# Simple_Motherboard.net
KiCad netlist of a schematic drawn in EAGLE
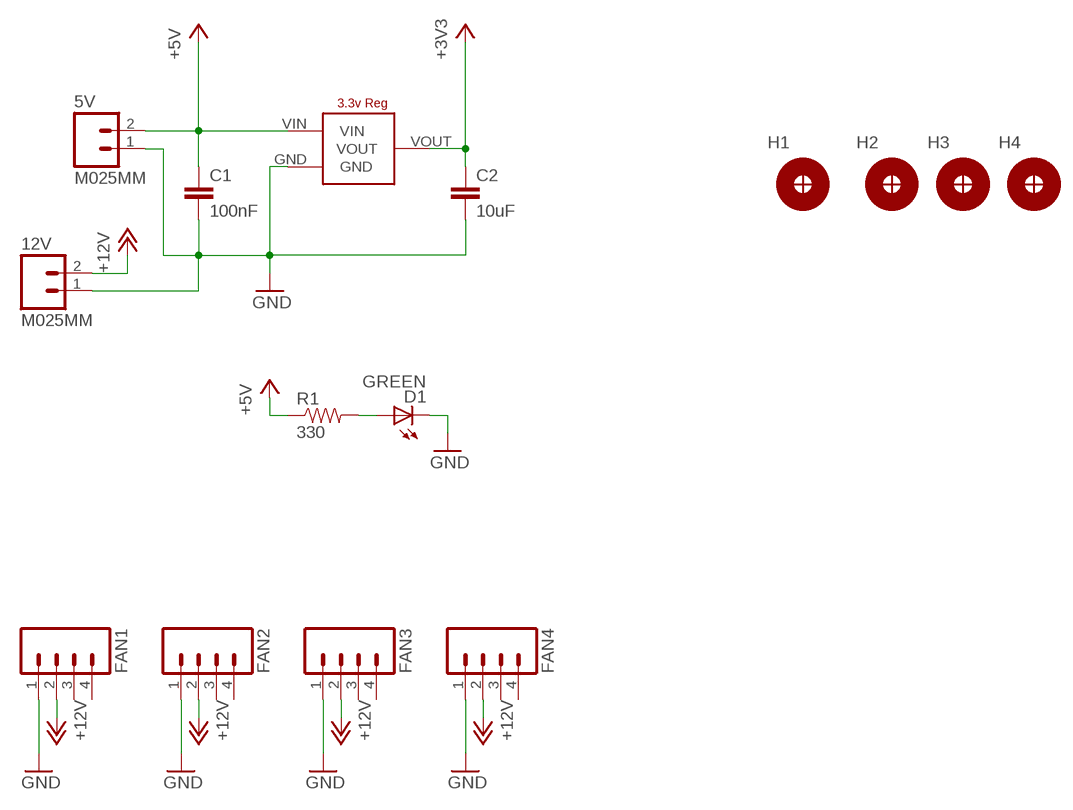
[diagram p0: schematic, sheet 1]
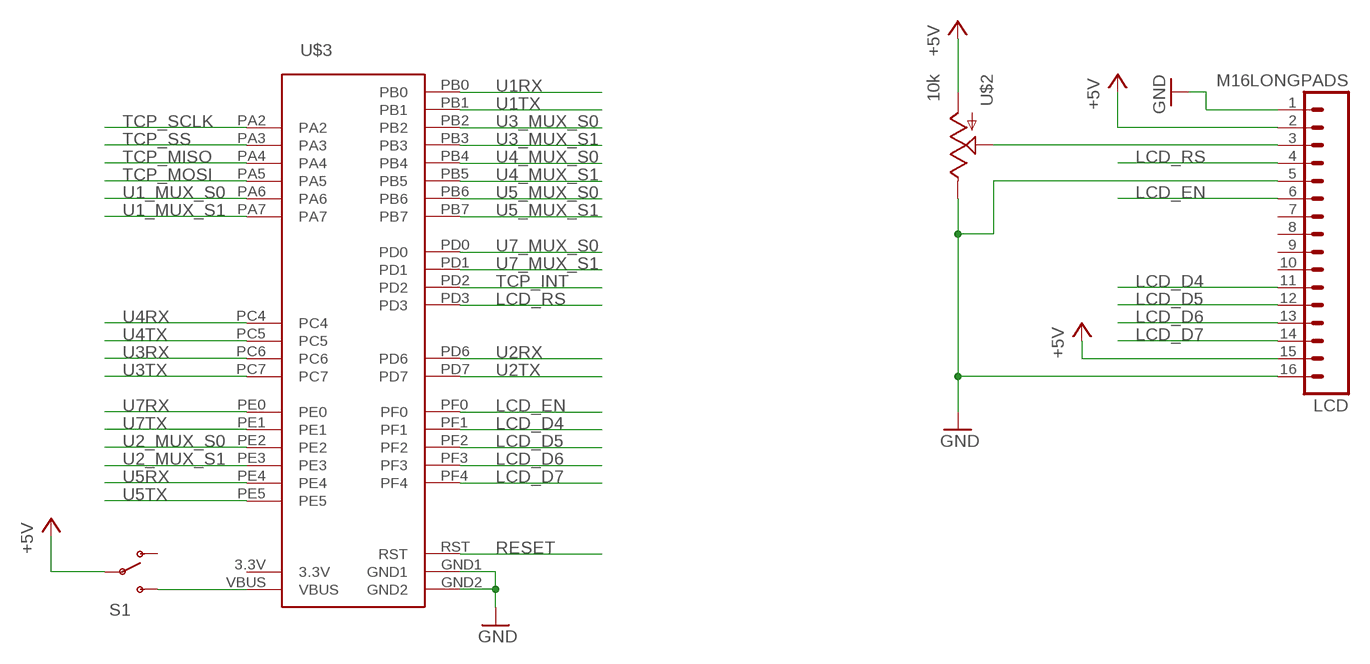
[diagram p1: schematic, sheet 2]
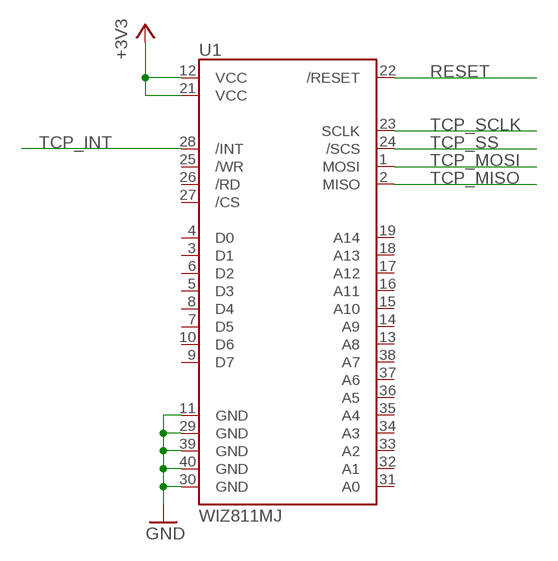
[diagram p2: schematic, sheet 3]
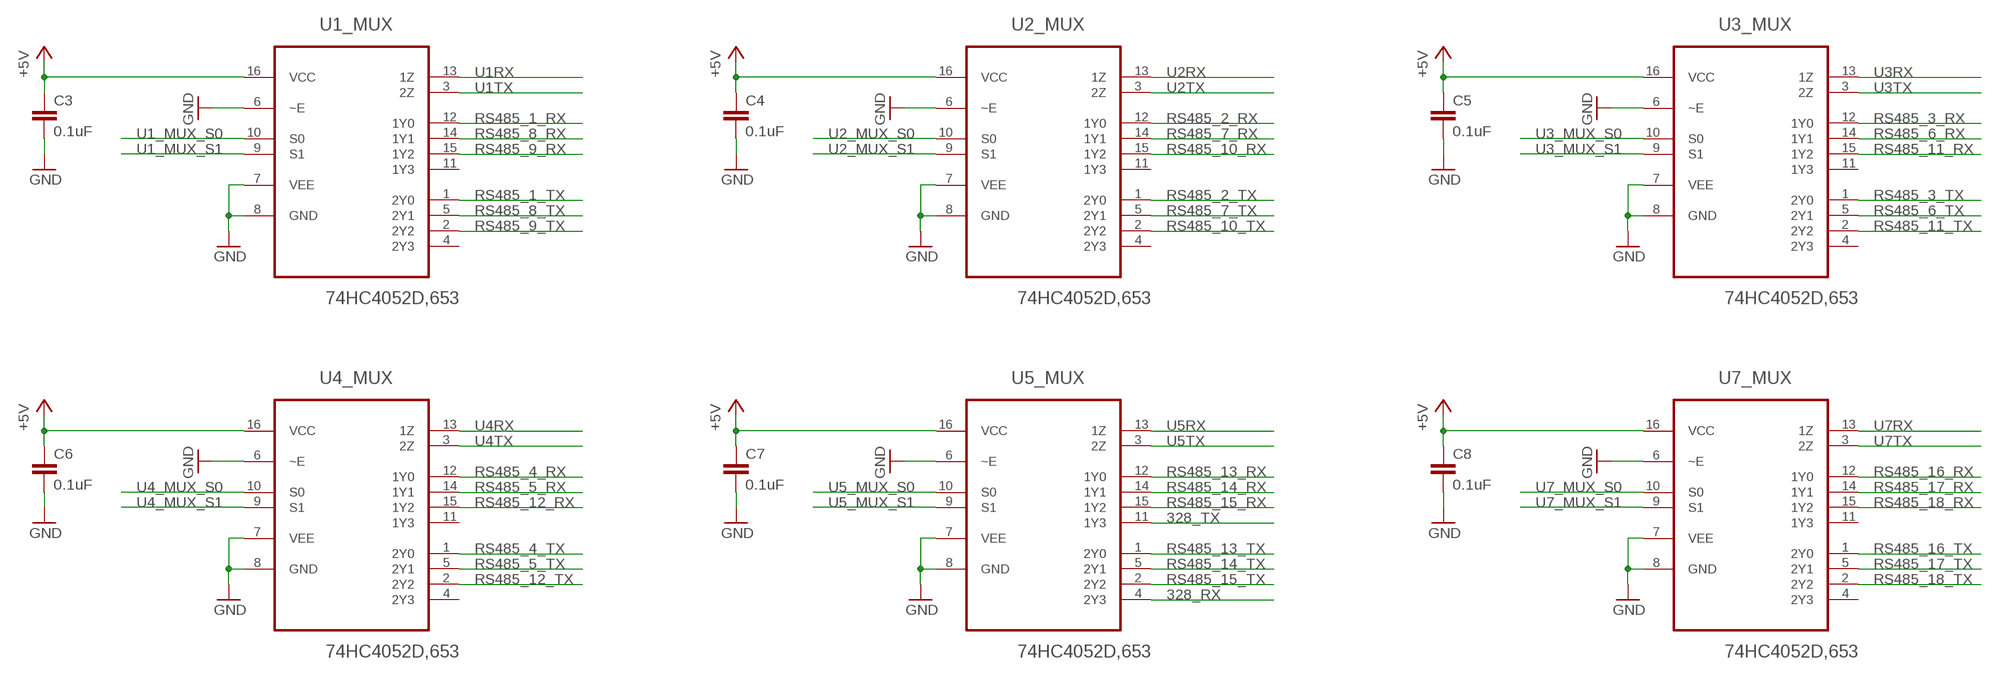
[diagram p3: schematic, sheet 4]
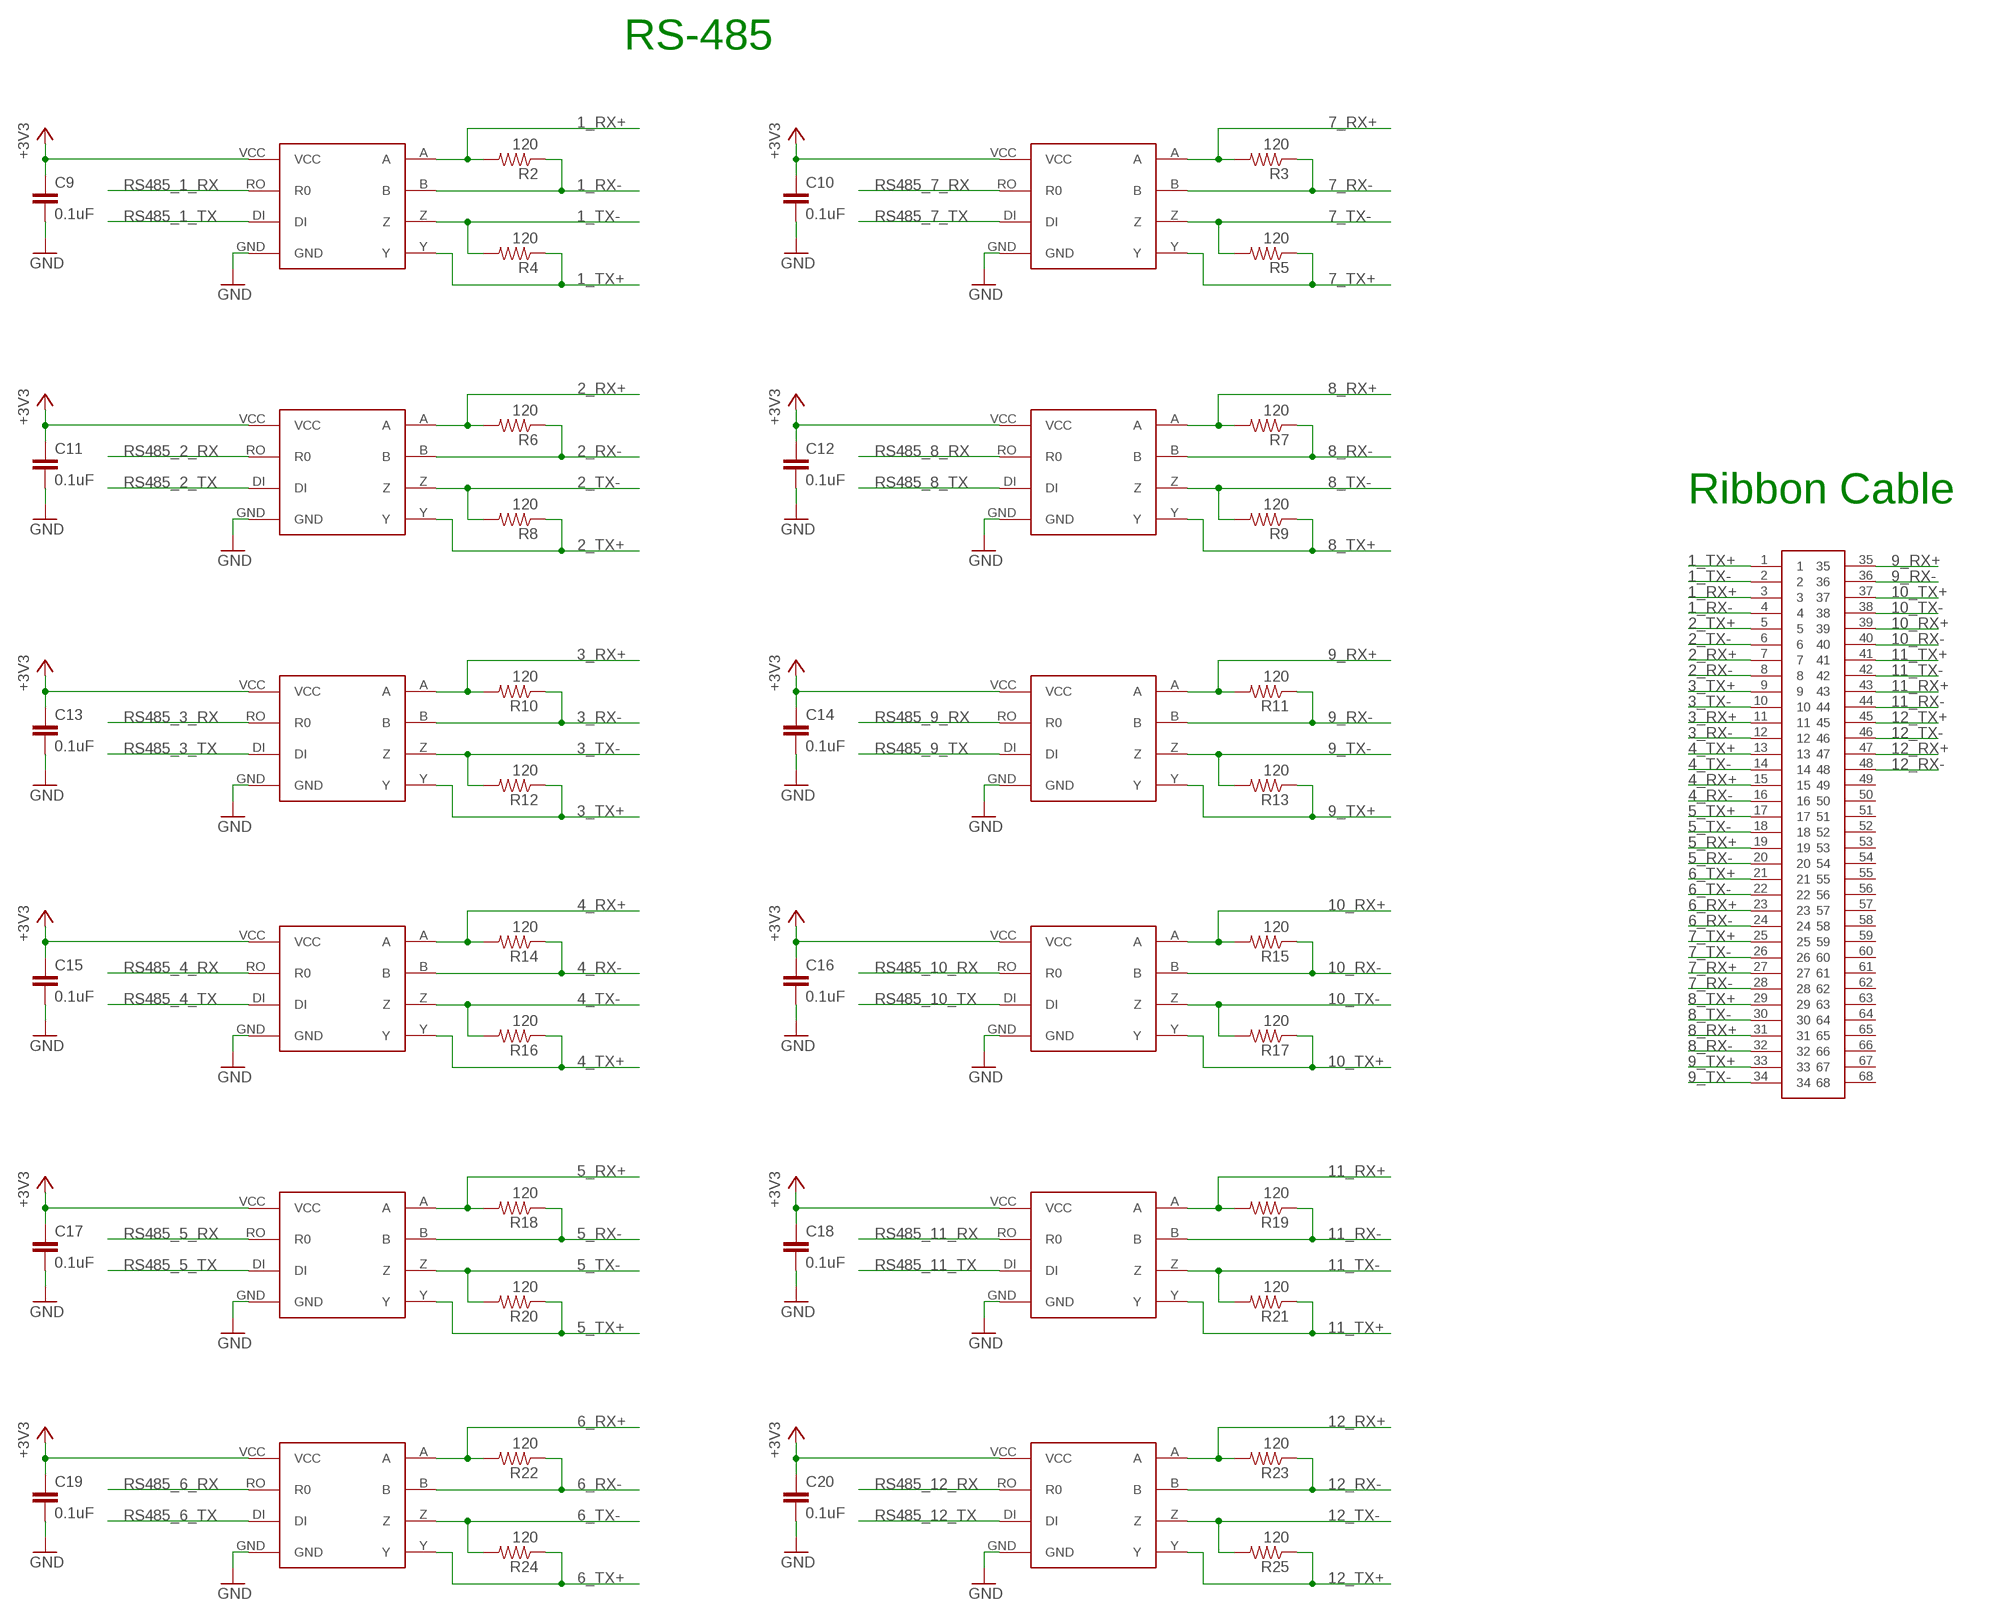
[diagram p4: schematic, sheet 5]
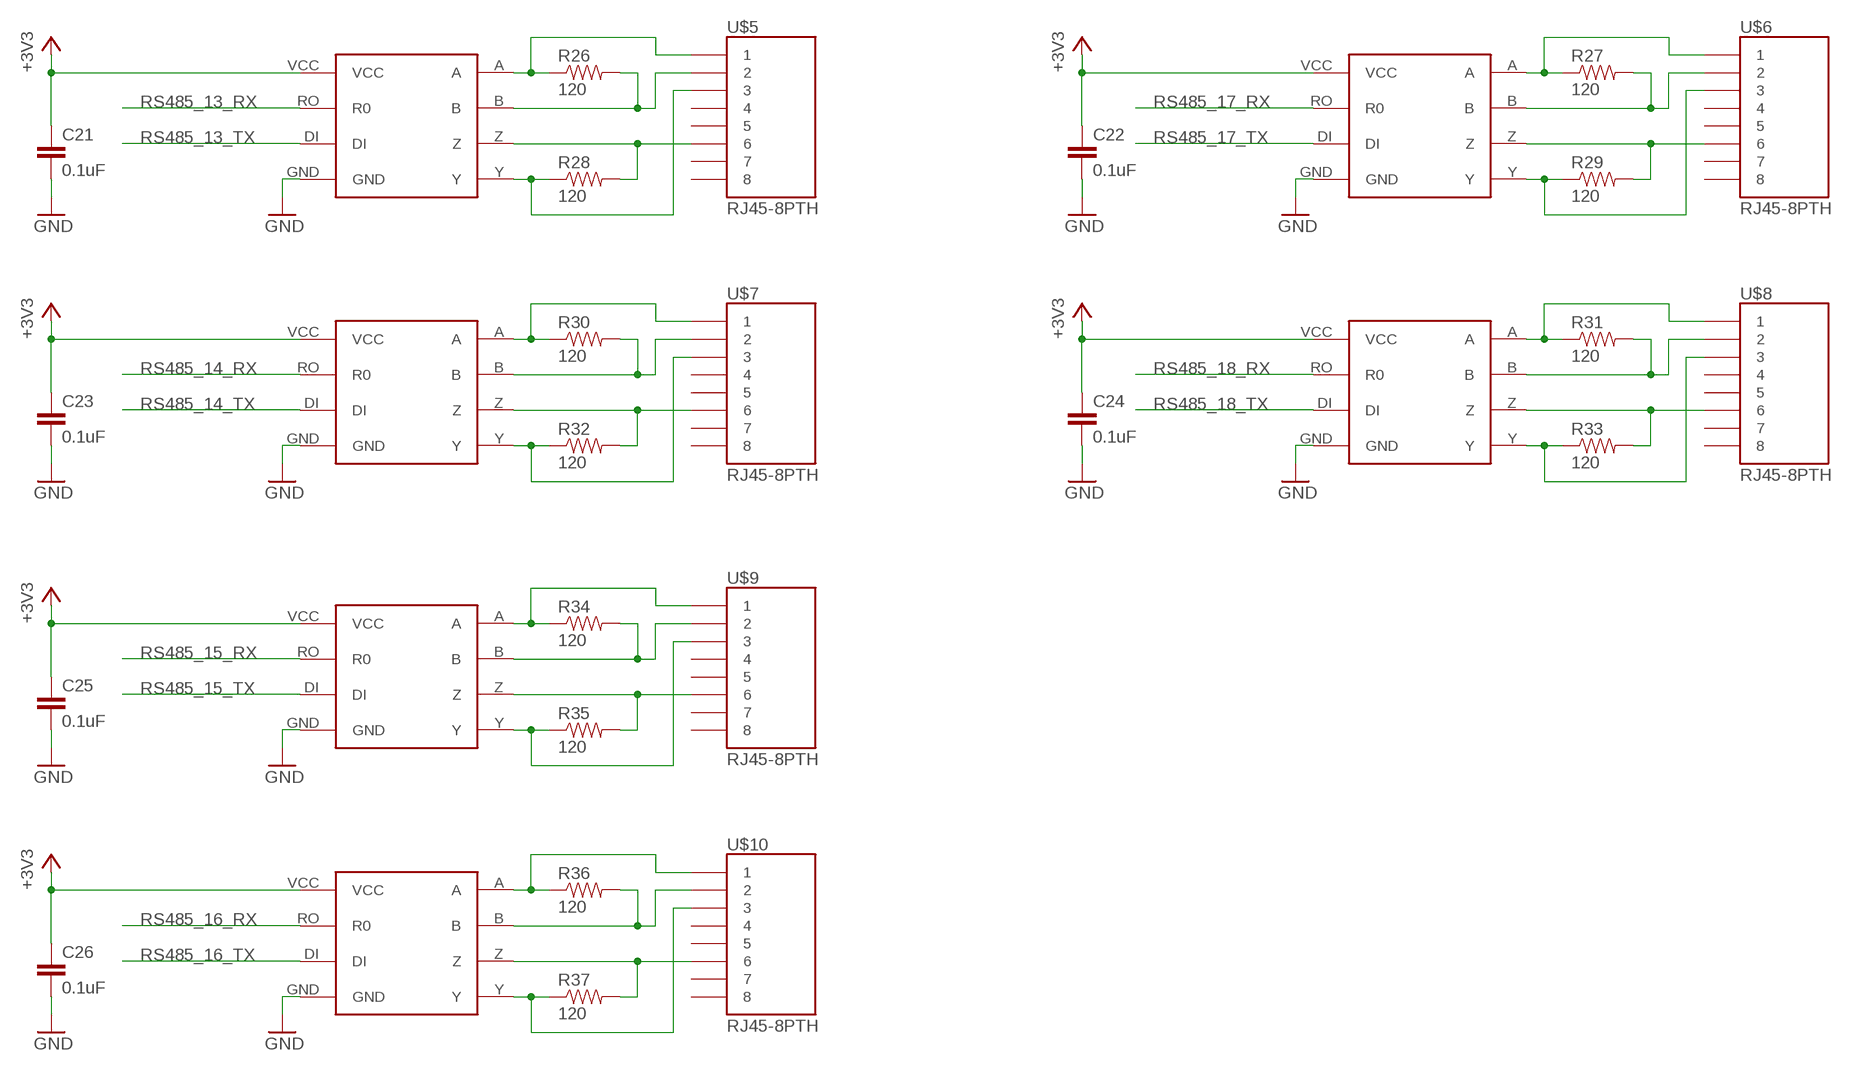
[diagram p5: schematic, sheet 6]
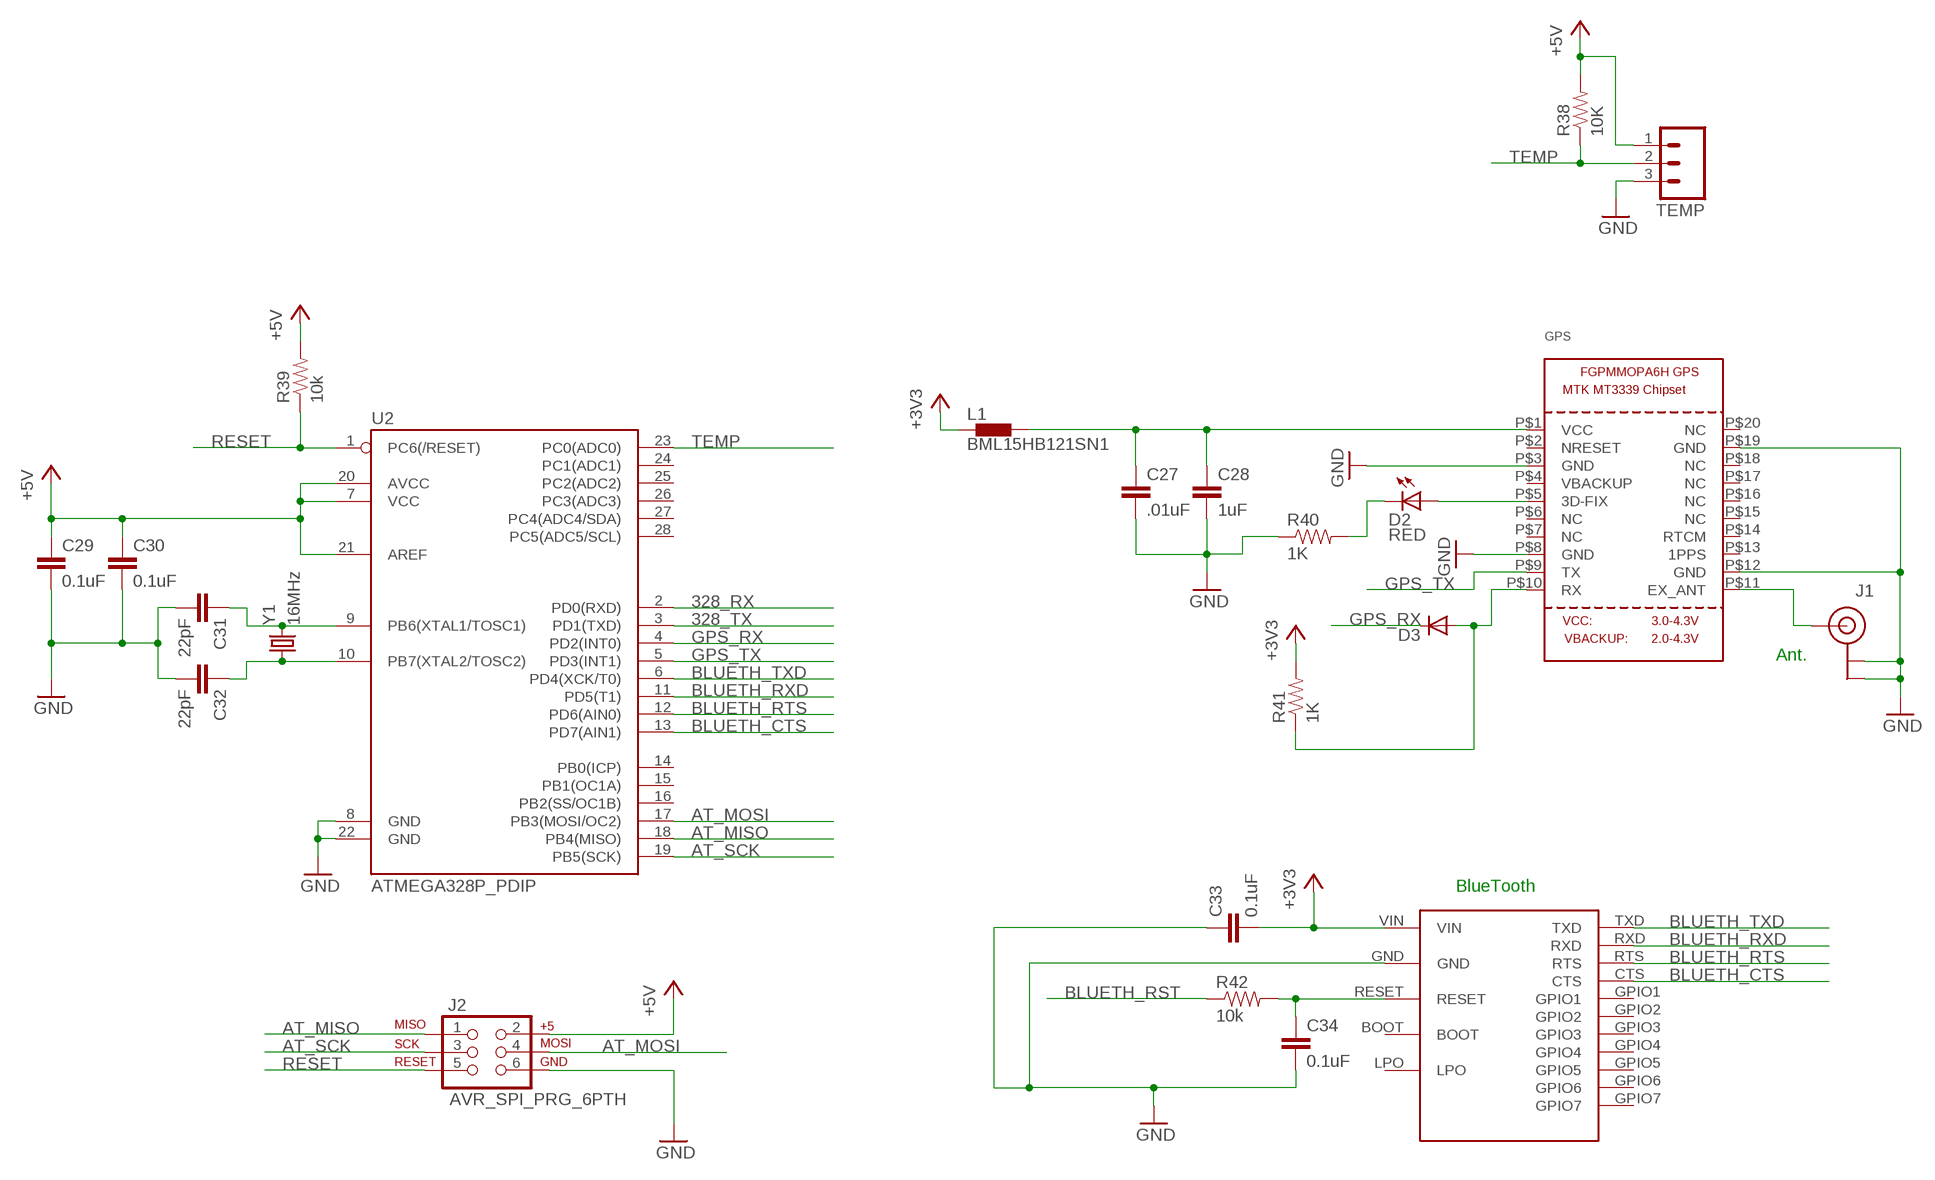
[diagram p6: schematic, sheet 7]

(export (version "E")
  (design (tool "Eeschema 10.0.6"))
  (components
    (comp (ref "LCD")
      (value "M16LONGPADS")
      (footprint "eagle-import:1X16_LONGPADS")
      (libsource (lib "eagle-import") (part "M16LONGPADS"))
    )
    (comp (ref "S1")
      (value "SWITCH-SPDTPTH_LOCK")
      (footprint "eagle-import:SWITCH-SPDT_LOCK.007S")
      (libsource (lib "eagle-import") (part "SWITCH-SPDTPTH_LOCK"))
    )
    (comp (ref "U$2")
      (value "10k")
      (footprint "eagle-import:3362U")
      (libsource (lib "eagle-import") (part "POT100K_3362U"))
    )
    (comp (ref "U$3")
      (value "STELLARIS-LAUNCHPADSTELLARIS-LAUNCHPAD-XL")
      (footprint "eagle-import:LAUNCHPAD-XL")
      (libsource (lib "eagle-import") (part "STELLARIS-LAUNCHPADSTELLARIS-LAUNCHPAD-XL"))
    )
    (comp (ref "U1")
      (value "WIZ811MJ")
      (footprint "eagle-import:WIZ811MJ")
      (libsource (lib "eagle-import") (part "WIZ811MJ"))
    )
    (comp (ref "C9")
      (value "0.1uF")
      (footprint "eagle-import:1206")
      (libsource (lib "eagle-import") (part "CAP1206"))
    )
    (comp (ref "C10")
      (value "0.1uF")
      (footprint "eagle-import:1206")
      (libsource (lib "eagle-import") (part "CAP1206"))
    )
    (comp (ref "C11")
      (value "0.1uF")
      (footprint "eagle-import:1206")
      (libsource (lib "eagle-import") (part "CAP1206"))
    )
    (comp (ref "C12")
      (value "0.1uF")
      (footprint "eagle-import:1206")
      (libsource (lib "eagle-import") (part "CAP1206"))
    )
    (comp (ref "C13")
      (value "0.1uF")
      (footprint "eagle-import:1206")
      (libsource (lib "eagle-import") (part "CAP1206"))
    )
    (comp (ref "C14")
      (value "0.1uF")
      (footprint "eagle-import:1206")
      (libsource (lib "eagle-import") (part "CAP1206"))
    )
    (comp (ref "C15")
      (value "0.1uF")
      (footprint "eagle-import:1206")
      (libsource (lib "eagle-import") (part "CAP1206"))
    )
    (comp (ref "C16")
      (value "0.1uF")
      (footprint "eagle-import:1206")
      (libsource (lib "eagle-import") (part "CAP1206"))
    )
    (comp (ref "C17")
      (value "0.1uF")
      (footprint "eagle-import:1206")
      (libsource (lib "eagle-import") (part "CAP1206"))
    )
    (comp (ref "C18")
      (value "0.1uF")
      (footprint "eagle-import:1206")
      (libsource (lib "eagle-import") (part "CAP1206"))
    )
    (comp (ref "C19")
      (value "0.1uF")
      (footprint "eagle-import:1206")
      (libsource (lib "eagle-import") (part "CAP1206"))
    )
    (comp (ref "C20")
      (value "0.1uF")
      (footprint "eagle-import:1206")
      (libsource (lib "eagle-import") (part "CAP1206"))
    )
    (comp (ref "R2")
      (value "120")
      (footprint "eagle-import:1206")
      (libsource (lib "eagle-import") (part "RESISTOR1206"))
    )
    (comp (ref "R3")
      (value "120")
      (footprint "eagle-import:1206")
      (libsource (lib "eagle-import") (part "RESISTOR1206"))
    )
    (comp (ref "R4")
      (value "120")
      (footprint "eagle-import:1206")
      (libsource (lib "eagle-import") (part "RESISTOR1206"))
    )
    (comp (ref "R5")
      (value "120")
      (footprint "eagle-import:1206")
      (libsource (lib "eagle-import") (part "RESISTOR1206"))
    )
    (comp (ref "R6")
      (value "120")
      (footprint "eagle-import:1206")
      (libsource (lib "eagle-import") (part "RESISTOR1206"))
    )
    (comp (ref "R7")
      (value "120")
      (footprint "eagle-import:1206")
      (libsource (lib "eagle-import") (part "RESISTOR1206"))
    )
    (comp (ref "R8")
      (value "120")
      (footprint "eagle-import:1206")
      (libsource (lib "eagle-import") (part "RESISTOR1206"))
    )
    (comp (ref "R9")
      (value "120")
      (footprint "eagle-import:1206")
      (libsource (lib "eagle-import") (part "RESISTOR1206"))
    )
    (comp (ref "R10")
      (value "120")
      (footprint "eagle-import:1206")
      (libsource (lib "eagle-import") (part "RESISTOR1206"))
    )
    (comp (ref "R11")
      (value "120")
      (footprint "eagle-import:1206")
      (libsource (lib "eagle-import") (part "RESISTOR1206"))
    )
    (comp (ref "R12")
      (value "120")
      (footprint "eagle-import:1206")
      (libsource (lib "eagle-import") (part "RESISTOR1206"))
    )
    (comp (ref "R13")
      (value "120")
      (footprint "eagle-import:1206")
      (libsource (lib "eagle-import") (part "RESISTOR1206"))
    )
    (comp (ref "R14")
      (value "120")
      (footprint "eagle-import:1206")
      (libsource (lib "eagle-import") (part "RESISTOR1206"))
    )
    (comp (ref "R15")
      (value "120")
      (footprint "eagle-import:1206")
      (libsource (lib "eagle-import") (part "RESISTOR1206"))
    )
    (comp (ref "R16")
      (value "120")
      (footprint "eagle-import:1206")
      (libsource (lib "eagle-import") (part "RESISTOR1206"))
    )
    (comp (ref "R17")
      (value "120")
      (footprint "eagle-import:1206")
      (libsource (lib "eagle-import") (part "RESISTOR1206"))
    )
    (comp (ref "R18")
      (value "120")
      (footprint "eagle-import:1206")
      (libsource (lib "eagle-import") (part "RESISTOR1206"))
    )
    (comp (ref "R19")
      (value "120")
      (footprint "eagle-import:1206")
      (libsource (lib "eagle-import") (part "RESISTOR1206"))
    )
    (comp (ref "R20")
      (value "120")
      (footprint "eagle-import:1206")
      (libsource (lib "eagle-import") (part "RESISTOR1206"))
    )
    (comp (ref "R21")
      (value "120")
      (footprint "eagle-import:1206")
      (libsource (lib "eagle-import") (part "RESISTOR1206"))
    )
    (comp (ref "R22")
      (value "120")
      (footprint "eagle-import:1206")
      (libsource (lib "eagle-import") (part "RESISTOR1206"))
    )
    (comp (ref "R23")
      (value "120")
      (footprint "eagle-import:1206")
      (libsource (lib "eagle-import") (part "RESISTOR1206"))
    )
    (comp (ref "R24")
      (value "120")
      (footprint "eagle-import:1206")
      (libsource (lib "eagle-import") (part "RESISTOR1206"))
    )
    (comp (ref "R25")
      (value "120")
      (footprint "eagle-import:1206")
      (libsource (lib "eagle-import") (part "RESISTOR1206"))
    )
    (comp (ref "RS_TRANS_1")
      (value "MAX3077")
      (footprint "eagle-import:MAX3070E")
      (libsource (lib "eagle-import") (part "MAX3077"))
    )
    (comp (ref "RS_TRANS_2")
      (value "MAX3077")
      (footprint "eagle-import:MAX3070E")
      (libsource (lib "eagle-import") (part "MAX3077"))
    )
    (comp (ref "RS_TRANS_3")
      (value "MAX3077")
      (footprint "eagle-import:MAX3070E")
      (libsource (lib "eagle-import") (part "MAX3077"))
    )
    (comp (ref "RS_TRANS_4")
      (value "MAX3077")
      (footprint "eagle-import:MAX3070E")
      (libsource (lib "eagle-import") (part "MAX3077"))
    )
    (comp (ref "RS_TRANS_5")
      (value "MAX3077")
      (footprint "eagle-import:MAX3070E")
      (libsource (lib "eagle-import") (part "MAX3077"))
    )
    (comp (ref "RS_TRANS_6")
      (value "MAX3077")
      (footprint "eagle-import:MAX3070E")
      (libsource (lib "eagle-import") (part "MAX3077"))
    )
    (comp (ref "RS_TRANS_7")
      (value "MAX3077")
      (footprint "eagle-import:MAX3070E")
      (libsource (lib "eagle-import") (part "MAX3077"))
    )
    (comp (ref "RS_TRANS_8")
      (value "MAX3077")
      (footprint "eagle-import:MAX3070E")
      (libsource (lib "eagle-import") (part "MAX3077"))
    )
    (comp (ref "RS_TRANS_9")
      (value "MAX3077")
      (footprint "eagle-import:MAX3070E")
      (libsource (lib "eagle-import") (part "MAX3077"))
    )
    (comp (ref "RS_TRANS_10")
      (value "MAX3077")
      (footprint "eagle-import:MAX3070E")
      (libsource (lib "eagle-import") (part "MAX3077"))
    )
    (comp (ref "RS_TRANS_11")
      (value "MAX3077")
      (footprint "eagle-import:MAX3070E")
      (libsource (lib "eagle-import") (part "MAX3077"))
    )
    (comp (ref "RS_TRANS_12")
      (value "MAX3077")
      (footprint "eagle-import:MAX3070E")
      (libsource (lib "eagle-import") (part "MAX3077"))
    )
    (comp (ref "U$4")
      (value "TB60050685100")
      (footprint "eagle-import:60050685100")
      (libsource (lib "eagle-import") (part "TB60050685100"))
    )
    (comp (ref "5V")
      (value "M025MM")
      (footprint "eagle-import:SCREWTERMINAL-5MM-2")
      (libsource (lib "eagle-import") (part "M025MM"))
    )
    (comp (ref "12V")
      (value "M025MM")
      (footprint "eagle-import:SCREWTERMINAL-5MM-2")
      (libsource (lib "eagle-import") (part "M025MM"))
    )
    (comp (ref "C1")
      (value "100nF")
      (footprint "eagle-import:1206")
      (libsource (lib "eagle-import") (part "CAP1206"))
    )
    (comp (ref "C2")
      (value "10uF")
      (footprint "eagle-import:1206")
      (libsource (lib "eagle-import") (part "CAP1206"))
    )
    (comp (ref "D1")
      (value "GREEN")
      (footprint "eagle-import:LED-1206")
      (libsource (lib "eagle-import") (part "LED-GREENLARGE"))
    )
    (comp (ref "FAN1")
      (value "M04LONGPADS")
      (footprint "eagle-import:1X04_LONGPADS")
      (libsource (lib "eagle-import") (part "M04LONGPADS"))
    )
    (comp (ref "FAN2")
      (value "M04LONGPADS")
      (footprint "eagle-import:1X04_LONGPADS")
      (libsource (lib "eagle-import") (part "M04LONGPADS"))
    )
    (comp (ref "FAN3")
      (value "M04LONGPADS")
      (footprint "eagle-import:1X04_LONGPADS")
      (libsource (lib "eagle-import") (part "M04LONGPADS"))
    )
    (comp (ref "FAN4")
      (value "M04LONGPADS")
      (footprint "eagle-import:1X04_LONGPADS")
      (libsource (lib "eagle-import") (part "M04LONGPADS"))
    )
    (comp (ref "H1")
      (value "H_MNTHOLE_#4")
      (footprint "eagle-import:H_MNTHOLE_#4")
      (libsource (lib "eagle-import") (part "H_MNTHOLE_#4"))
    )
    (comp (ref "H2")
      (value "H_MNTHOLE_#4")
      (footprint "eagle-import:H_MNTHOLE_#4")
      (libsource (lib "eagle-import") (part "H_MNTHOLE_#4"))
    )
    (comp (ref "H3")
      (value "H_MNTHOLE_#4")
      (footprint "eagle-import:H_MNTHOLE_#4")
      (libsource (lib "eagle-import") (part "H_MNTHOLE_#4"))
    )
    (comp (ref "H4")
      (value "H_MNTHOLE_#4")
      (footprint "eagle-import:H_MNTHOLE_#4")
      (libsource (lib "eagle-import") (part "H_MNTHOLE_#4"))
    )
    (comp (ref "R1")
      (value "330")
      (footprint "eagle-import:1206")
      (libsource (lib "eagle-import") (part "RESISTOR1206"))
    )
    (comp (ref "U$1")
      (value "LD1117")
      (footprint "eagle-import:LD1117SOT-223")
      (libsource (lib "eagle-import") (part "LD1117"))
    )
    (comp (ref "C3")
      (value "0.1uF")
      (footprint "eagle-import:1206")
      (libsource (lib "eagle-import") (part "CAP1206"))
    )
    (comp (ref "C4")
      (value "0.1uF")
      (footprint "eagle-import:1206")
      (libsource (lib "eagle-import") (part "CAP1206"))
    )
    (comp (ref "C5")
      (value "0.1uF")
      (footprint "eagle-import:1206")
      (libsource (lib "eagle-import") (part "CAP1206"))
    )
    (comp (ref "C6")
      (value "0.1uF")
      (footprint "eagle-import:1206")
      (libsource (lib "eagle-import") (part "CAP1206"))
    )
    (comp (ref "C7")
      (value "0.1uF")
      (footprint "eagle-import:1206")
      (libsource (lib "eagle-import") (part "CAP1206"))
    )
    (comp (ref "C8")
      (value "0.1uF")
      (footprint "eagle-import:1206")
      (libsource (lib "eagle-import") (part "CAP1206"))
    )
    (comp (ref "U1_MUX")
      (value "74HC4052D,653")
      (footprint "eagle-import:SOIC127P600X175-16N")
      (libsource (lib "eagle-import") (part "74HC4052D,653"))
    )
    (comp (ref "U2_MUX")
      (value "74HC4052D,653")
      (footprint "eagle-import:SOIC127P600X175-16N")
      (libsource (lib "eagle-import") (part "74HC4052D,653"))
    )
    (comp (ref "U3_MUX")
      (value "74HC4052D,653")
      (footprint "eagle-import:SOIC127P600X175-16N")
      (libsource (lib "eagle-import") (part "74HC4052D,653"))
    )
    (comp (ref "U4_MUX")
      (value "74HC4052D,653")
      (footprint "eagle-import:SOIC127P600X175-16N")
      (libsource (lib "eagle-import") (part "74HC4052D,653"))
    )
    (comp (ref "U5_MUX")
      (value "74HC4052D,653")
      (footprint "eagle-import:SOIC127P600X175-16N")
      (libsource (lib "eagle-import") (part "74HC4052D,653"))
    )
    (comp (ref "U7_MUX")
      (value "74HC4052D,653")
      (footprint "eagle-import:SOIC127P600X175-16N")
      (libsource (lib "eagle-import") (part "74HC4052D,653"))
    )
    (comp (ref "BLUETOOTH")
      (value "SPBT2632C2A")
      (footprint "eagle-import:SPBT2632C2A")
      (libsource (lib "eagle-import") (part "SPBT2632C2A"))
    )
    (comp (ref "C27")
      (value ".01uF")
      (footprint "eagle-import:1206")
      (libsource (lib "eagle-import") (part "CAP1206"))
    )
    (comp (ref "C28")
      (value "1uF")
      (footprint "eagle-import:1206")
      (libsource (lib "eagle-import") (part "CAP1206"))
    )
    (comp (ref "C29")
      (value "0.1uF")
      (footprint "eagle-import:1206")
      (libsource (lib "eagle-import") (part "CAP1206"))
    )
    (comp (ref "C30")
      (value "0.1uF")
      (footprint "eagle-import:1206")
      (libsource (lib "eagle-import") (part "CAP1206"))
    )
    (comp (ref "C31")
      (value "22pF")
      (footprint "eagle-import:1206")
      (libsource (lib "eagle-import") (part "CAP1206"))
    )
    (comp (ref "C32")
      (value "22pF")
      (footprint "eagle-import:1206")
      (libsource (lib "eagle-import") (part "CAP1206"))
    )
    (comp (ref "C33")
      (value "0.1uF")
      (footprint "eagle-import:1206")
      (libsource (lib "eagle-import") (part "CAP1206"))
    )
    (comp (ref "C34")
      (value "0.1uF")
      (footprint "eagle-import:1206")
      (libsource (lib "eagle-import") (part "CAP1206"))
    )
    (comp (ref "D2")
      (value "RED")
      (footprint "eagle-import:LED-1206")
      (libsource (lib "eagle-import") (part "LED-RED1206"))
    )
    (comp (ref "D3")
      (value "DIODEHV")
      (footprint "eagle-import:DIODE-HV")
      (libsource (lib "eagle-import") (part "DIODEHV"))
    )
    (comp (ref "GPS")
      (value "GPS_FGPMMOPA6H")
      (footprint "eagle-import:FGPMMOPA6H")
      (libsource (lib "eagle-import") (part "GPS_FGPMMOPA6H"))
    )
    (comp (ref "J1")
      (value "U.FL")
      (footprint "eagle-import:U.FL")
      (libsource (lib "eagle-import") (part "U.FL"))
    )
    (comp (ref "J2")
      (value "AVR_SPI_PRG_6PTH")
      (footprint "eagle-import:2X3")
      (libsource (lib "eagle-import") (part "AVR_SPI_PRG_6PTH"))
    )
    (comp (ref "L1")
      (value "BML15HB121SN1")
      (footprint "eagle-import:0402")
      (libsource (lib "eagle-import") (part "BML15HB121SN1"))
    )
    (comp (ref "R38")
      (value "10K")
      (footprint "eagle-import:1206")
      (libsource (lib "eagle-import") (part "RESISTOR1206"))
    )
    (comp (ref "R39")
      (value "10k")
      (footprint "eagle-import:1206")
      (libsource (lib "eagle-import") (part "SparkFun-Resistors_RESISTOR1206"))
    )
    (comp (ref "R40")
      (value "1K")
      (footprint "eagle-import:1206")
      (libsource (lib "eagle-import") (part "RESISTOR1206"))
    )
    (comp (ref "R41")
      (value "1K")
      (footprint "eagle-import:1206")
      (libsource (lib "eagle-import") (part "RESISTOR1206"))
    )
    (comp (ref "R42")
      (value "10k")
      (footprint "eagle-import:1206")
      (libsource (lib "eagle-import") (part "RESISTOR1206"))
    )
    (comp (ref "TEMP")
      (value "M03POLAR")
      (footprint "eagle-import:MOLEX-1X3")
      (libsource (lib "eagle-import") (part "M03POLAR"))
    )
    (comp (ref "U2")
      (value "ATMEGA328P_PDIP")
      (footprint "eagle-import:DIL28-3")
      (libsource (lib "eagle-import") (part "ATMEGA328P_PDIP"))
    )
    (comp (ref "Y1")
      (value "16MHz")
      (footprint "eagle-import:HC49US")
      (libsource (lib "eagle-import") (part "CRYSTALHC49US"))
    )
    (comp (ref "C21")
      (value "0.1uF")
      (footprint "eagle-import:1206")
      (libsource (lib "eagle-import") (part "CAP1206"))
    )
    (comp (ref "C22")
      (value "0.1uF")
      (footprint "eagle-import:1206")
      (libsource (lib "eagle-import") (part "CAP1206"))
    )
    (comp (ref "C23")
      (value "0.1uF")
      (footprint "eagle-import:1206")
      (libsource (lib "eagle-import") (part "CAP1206"))
    )
    (comp (ref "C24")
      (value "0.1uF")
      (footprint "eagle-import:1206")
      (libsource (lib "eagle-import") (part "CAP1206"))
    )
    (comp (ref "C25")
      (value "0.1uF")
      (footprint "eagle-import:1206")
      (libsource (lib "eagle-import") (part "CAP1206"))
    )
    (comp (ref "C26")
      (value "0.1uF")
      (footprint "eagle-import:1206")
      (libsource (lib "eagle-import") (part "CAP1206"))
    )
    (comp (ref "R26")
      (value "120")
      (footprint "eagle-import:1206")
      (libsource (lib "eagle-import") (part "RESISTOR1206"))
    )
    (comp (ref "R27")
      (value "120")
      (footprint "eagle-import:1206")
      (libsource (lib "eagle-import") (part "RESISTOR1206"))
    )
    (comp (ref "R28")
      (value "120")
      (footprint "eagle-import:1206")
      (libsource (lib "eagle-import") (part "RESISTOR1206"))
    )
    (comp (ref "R29")
      (value "120")
      (footprint "eagle-import:1206")
      (libsource (lib "eagle-import") (part "RESISTOR1206"))
    )
    (comp (ref "R30")
      (value "120")
      (footprint "eagle-import:1206")
      (libsource (lib "eagle-import") (part "RESISTOR1206"))
    )
    (comp (ref "R31")
      (value "120")
      (footprint "eagle-import:1206")
      (libsource (lib "eagle-import") (part "RESISTOR1206"))
    )
    (comp (ref "R32")
      (value "120")
      (footprint "eagle-import:1206")
      (libsource (lib "eagle-import") (part "RESISTOR1206"))
    )
    (comp (ref "R33")
      (value "120")
      (footprint "eagle-import:1206")
      (libsource (lib "eagle-import") (part "RESISTOR1206"))
    )
    (comp (ref "R34")
      (value "120")
      (footprint "eagle-import:1206")
      (libsource (lib "eagle-import") (part "RESISTOR1206"))
    )
    (comp (ref "R35")
      (value "120")
      (footprint "eagle-import:1206")
      (libsource (lib "eagle-import") (part "RESISTOR1206"))
    )
    (comp (ref "R36")
      (value "120")
      (footprint "eagle-import:1206")
      (libsource (lib "eagle-import") (part "RESISTOR1206"))
    )
    (comp (ref "R37")
      (value "120")
      (footprint "eagle-import:1206")
      (libsource (lib "eagle-import") (part "RESISTOR1206"))
    )
    (comp (ref "RS-485-1")
      (value "MAX3077")
      (footprint "eagle-import:MAX3070E")
      (libsource (lib "eagle-import") (part "MAX3077"))
    )
    (comp (ref "RS-485-2")
      (value "MAX3077")
      (footprint "eagle-import:MAX3070E")
      (libsource (lib "eagle-import") (part "MAX3077"))
    )
    (comp (ref "RS-485-3")
      (value "MAX3077")
      (footprint "eagle-import:MAX3070E")
      (libsource (lib "eagle-import") (part "MAX3077"))
    )
    (comp (ref "RS-485-4")
      (value "MAX3077")
      (footprint "eagle-import:MAX3070E")
      (libsource (lib "eagle-import") (part "MAX3077"))
    )
    (comp (ref "RS-485-5")
      (value "MAX3077")
      (footprint "eagle-import:MAX3070E")
      (libsource (lib "eagle-import") (part "MAX3077"))
    )
    (comp (ref "RS-485-6")
      (value "MAX3077")
      (footprint "eagle-import:MAX3070E")
      (libsource (lib "eagle-import") (part "MAX3077"))
    )
    (comp (ref "U$5")
      (value "RJ45-8PTH")
      (footprint "eagle-import:RJ45-8")
      (libsource (lib "eagle-import") (part "RJ45-8PTH"))
    )
    (comp (ref "U$6")
      (value "RJ45-8PTH")
      (footprint "eagle-import:RJ45-8")
      (libsource (lib "eagle-import") (part "RJ45-8PTH"))
    )
    (comp (ref "U$7")
      (value "RJ45-8PTH")
      (footprint "eagle-import:RJ45-8")
      (libsource (lib "eagle-import") (part "RJ45-8PTH"))
    )
    (comp (ref "U$8")
      (value "RJ45-8PTH")
      (footprint "eagle-import:RJ45-8")
      (libsource (lib "eagle-import") (part "RJ45-8PTH"))
    )
    (comp (ref "U$9")
      (value "RJ45-8PTH")
      (footprint "eagle-import:RJ45-8")
      (libsource (lib "eagle-import") (part "RJ45-8PTH"))
    )
    (comp (ref "U$10")
      (value "RJ45-8PTH")
      (footprint "eagle-import:RJ45-8")
      (libsource (lib "eagle-import") (part "RJ45-8PTH"))
    )
  )
  (nets
    (net (code "1") (name "+3V3") (class "Default")
      (node (ref "BLUETOOTH") (pin "VIN") (pinfunction "VIN_VIN") (pintype "bidirectional"))
      (node (ref "C10") (pin "1") (pinfunction "1_1") (pintype "passive"))
      (node (ref "C11") (pin "1") (pinfunction "1_1") (pintype "passive"))
      (node (ref "C12") (pin "1") (pinfunction "1_1") (pintype "passive"))
      (node (ref "C13") (pin "1") (pinfunction "1_1") (pintype "passive"))
      (node (ref "C14") (pin "1") (pinfunction "1_1") (pintype "passive"))
      (node (ref "C15") (pin "1") (pinfunction "1_1") (pintype "passive"))
      (node (ref "C16") (pin "1") (pinfunction "1_1") (pintype "passive"))
      (node (ref "C17") (pin "1") (pinfunction "1_1") (pintype "passive"))
      (node (ref "C18") (pin "1") (pinfunction "1_1") (pintype "passive"))
      (node (ref "C19") (pin "1") (pinfunction "1_1") (pintype "passive"))
      (node (ref "C2") (pin "1") (pinfunction "1_1") (pintype "passive"))
      (node (ref "C20") (pin "1") (pinfunction "1_1") (pintype "passive"))
      (node (ref "C21") (pin "1") (pinfunction "1_1") (pintype "passive"))
      (node (ref "C22") (pin "1") (pinfunction "1_1") (pintype "passive"))
      (node (ref "C23") (pin "1") (pinfunction "1_1") (pintype "passive"))
      (node (ref "C24") (pin "1") (pinfunction "1_1") (pintype "passive"))
      (node (ref "C25") (pin "1") (pinfunction "1_1") (pintype "passive"))
      (node (ref "C26") (pin "1") (pinfunction "1_1") (pintype "passive"))
      (node (ref "C33") (pin "2") (pinfunction "2_2") (pintype "passive"))
      (node (ref "C9") (pin "1") (pinfunction "1_1") (pintype "passive"))
      (node (ref "L1") (pin "1") (pinfunction "1_1") (pintype "passive"))
      (node (ref "R41") (pin "2") (pinfunction "2_2") (pintype "passive"))
      (node (ref "RS-485-1") (pin "VCC") (pinfunction "VCC_VCC") (pintype "bidirectional"))
      (node (ref "RS-485-2") (pin "VCC") (pinfunction "VCC_VCC") (pintype "bidirectional"))
      (node (ref "RS-485-3") (pin "VCC") (pinfunction "VCC_VCC") (pintype "bidirectional"))
      (node (ref "RS-485-4") (pin "VCC") (pinfunction "VCC_VCC") (pintype "bidirectional"))
      (node (ref "RS-485-5") (pin "VCC") (pinfunction "VCC_VCC") (pintype "bidirectional"))
      (node (ref "RS-485-6") (pin "VCC") (pinfunction "VCC_VCC") (pintype "bidirectional"))
      (node (ref "RS_TRANS_1") (pin "VCC") (pinfunction "VCC_VCC") (pintype "bidirectional"))
      (node (ref "RS_TRANS_10") (pin "VCC") (pinfunction "VCC_VCC") (pintype "bidirectional"))
      (node (ref "RS_TRANS_11") (pin "VCC") (pinfunction "VCC_VCC") (pintype "bidirectional"))
      (node (ref "RS_TRANS_12") (pin "VCC") (pinfunction "VCC_VCC") (pintype "bidirectional"))
      (node (ref "RS_TRANS_2") (pin "VCC") (pinfunction "VCC_VCC") (pintype "bidirectional"))
      (node (ref "RS_TRANS_3") (pin "VCC") (pinfunction "VCC_VCC") (pintype "bidirectional"))
      (node (ref "RS_TRANS_4") (pin "VCC") (pinfunction "VCC_VCC") (pintype "bidirectional"))
      (node (ref "RS_TRANS_5") (pin "VCC") (pinfunction "VCC_VCC") (pintype "bidirectional"))
      (node (ref "RS_TRANS_6") (pin "VCC") (pinfunction "VCC_VCC") (pintype "bidirectional"))
      (node (ref "RS_TRANS_7") (pin "VCC") (pinfunction "VCC_VCC") (pintype "bidirectional"))
      (node (ref "RS_TRANS_8") (pin "VCC") (pinfunction "VCC_VCC") (pintype "bidirectional"))
      (node (ref "RS_TRANS_9") (pin "VCC") (pinfunction "VCC_VCC") (pintype "bidirectional"))
      (node (ref "U$1") (pin "VOUT") (pinfunction "VOUT_VOUT") (pintype "bidirectional"))
      (node (ref "U1") (pin "12") (pinfunction "VCC_12") (pintype "bidirectional"))
      (node (ref "U1") (pin "21") (pinfunction "VCC_21") (pintype "bidirectional"))
    )
    (net (code "2") (name "+5V") (class "Default")
      (node (ref "5V") (pin "2") (pinfunction "2_2") (pintype "passive"))
      (node (ref "C1") (pin "1") (pinfunction "1_1") (pintype "passive"))
      (node (ref "C29") (pin "1") (pinfunction "1_1") (pintype "passive"))
      (node (ref "C3") (pin "1") (pinfunction "1_1") (pintype "passive"))
      (node (ref "C30") (pin "1") (pinfunction "1_1") (pintype "passive"))
      (node (ref "C4") (pin "1") (pinfunction "1_1") (pintype "passive"))
      (node (ref "C5") (pin "1") (pinfunction "1_1") (pintype "passive"))
      (node (ref "C6") (pin "1") (pinfunction "1_1") (pintype "passive"))
      (node (ref "C7") (pin "1") (pinfunction "1_1") (pintype "passive"))
      (node (ref "C8") (pin "1") (pinfunction "1_1") (pintype "passive"))
      (node (ref "J2") (pin "2") (pinfunction "2_2") (pintype "passive"))
      (node (ref "LCD") (pin "15") (pinfunction "15_15") (pintype "passive"))
      (node (ref "LCD") (pin "2") (pinfunction "2_2") (pintype "passive"))
      (node (ref "R1") (pin "1") (pinfunction "1_1") (pintype "passive"))
      (node (ref "R38") (pin "2") (pinfunction "2_2") (pintype "passive"))
      (node (ref "R39") (pin "2") (pinfunction "2_2") (pintype "passive"))
      (node (ref "S1") (pin "2") (pinfunction "P_2") (pintype "passive"))
      (node (ref "TEMP") (pin "1") (pinfunction "1_1") (pintype "passive"))
      (node (ref "U$1") (pin "VIN") (pinfunction "VIN_VIN") (pintype "bidirectional"))
      (node (ref "U$2") (pin "P$3") (pinfunction "A_P$3") (pintype "passive"))
      (node (ref "U1_MUX") (pin "16") (pinfunction "VCC_16") (pintype "power_in"))
      (node (ref "U2") (pin "20") (pinfunction "AVCC_20") (pintype "bidirectional"))
      (node (ref "U2") (pin "21") (pinfunction "AREF_21") (pintype "bidirectional"))
      (node (ref "U2") (pin "7") (pinfunction "VCC_7") (pintype "bidirectional"))
      (node (ref "U2_MUX") (pin "16") (pinfunction "VCC_16") (pintype "power_in"))
      (node (ref "U3_MUX") (pin "16") (pinfunction "VCC_16") (pintype "power_in"))
      (node (ref "U4_MUX") (pin "16") (pinfunction "VCC_16") (pintype "power_in"))
      (node (ref "U5_MUX") (pin "16") (pinfunction "VCC_16") (pintype "power_in"))
      (node (ref "U7_MUX") (pin "16") (pinfunction "VCC_16") (pintype "power_in"))
    )
    (net (code "3") (name "+12V") (class "Default")
      (node (ref "12V") (pin "2") (pinfunction "2_2") (pintype "passive"))
      (node (ref "FAN1") (pin "2") (pinfunction "2_2") (pintype "passive"))
      (node (ref "FAN2") (pin "2") (pinfunction "2_2") (pintype "passive"))
      (node (ref "FAN3") (pin "2") (pinfunction "2_2") (pintype "passive"))
      (node (ref "FAN4") (pin "2") (pinfunction "2_2") (pintype "passive"))
    )
    (net (code "4") (name "1_RX+") (class "Default")
      (node (ref "R2") (pin "2") (pinfunction "2_2") (pintype "passive"))
      (node (ref "RS_TRANS_1") (pin "A") (pinfunction "A_A") (pintype "bidirectional"))
      (node (ref "U$4") (pin "3") (pinfunction "3_3") (pintype "bidirectional"))
    )
    (net (code "5") (name "1_RX-") (class "Default")
      (node (ref "R2") (pin "1") (pinfunction "1_1") (pintype "passive"))
      (node (ref "RS_TRANS_1") (pin "B") (pinfunction "B_B") (pintype "bidirectional"))
      (node (ref "U$4") (pin "4") (pinfunction "4_4") (pintype "bidirectional"))
    )
    (net (code "6") (name "1_TX+") (class "Default")
      (node (ref "R4") (pin "1") (pinfunction "1_1") (pintype "passive"))
      (node (ref "RS_TRANS_1") (pin "Y") (pinfunction "Y_Y") (pintype "bidirectional"))
      (node (ref "U$4") (pin "1") (pinfunction "1_1") (pintype "bidirectional"))
    )
    (net (code "7") (name "1_TX-") (class "Default")
      (node (ref "R4") (pin "2") (pinfunction "2_2") (pintype "passive"))
      (node (ref "RS_TRANS_1") (pin "Z") (pinfunction "Z_Z") (pintype "bidirectional"))
      (node (ref "U$4") (pin "2") (pinfunction "2_2") (pintype "bidirectional"))
    )
    (net (code "8") (name "2_RX+") (class "Default")
      (node (ref "R6") (pin "2") (pinfunction "2_2") (pintype "passive"))
      (node (ref "RS_TRANS_3") (pin "A") (pinfunction "A_A") (pintype "bidirectional"))
      (node (ref "U$4") (pin "7") (pinfunction "7_7") (pintype "bidirectional"))
    )
    (net (code "9") (name "2_RX-") (class "Default")
      (node (ref "R6") (pin "1") (pinfunction "1_1") (pintype "passive"))
      (node (ref "RS_TRANS_3") (pin "B") (pinfunction "B_B") (pintype "bidirectional"))
      (node (ref "U$4") (pin "8") (pinfunction "8_8") (pintype "bidirectional"))
    )
    (net (code "10") (name "2_TX+") (class "Default")
      (node (ref "R8") (pin "1") (pinfunction "1_1") (pintype "passive"))
      (node (ref "RS_TRANS_3") (pin "Y") (pinfunction "Y_Y") (pintype "bidirectional"))
      (node (ref "U$4") (pin "5") (pinfunction "5_5") (pintype "bidirectional"))
    )
    (net (code "11") (name "2_TX-") (class "Default")
      (node (ref "R8") (pin "2") (pinfunction "2_2") (pintype "passive"))
      (node (ref "RS_TRANS_3") (pin "Z") (pinfunction "Z_Z") (pintype "bidirectional"))
      (node (ref "U$4") (pin "6") (pinfunction "6_6") (pintype "bidirectional"))
    )
    (net (code "12") (name "3.3V") (class "Default")
      (node (ref "U$3") (pin "3.3V") (pinfunction "3.3V_3.3V") (pintype "power_in"))
    )
    (net (code "13") (name "3_RX+") (class "Default")
      (node (ref "R10") (pin "2") (pinfunction "2_2") (pintype "passive"))
      (node (ref "RS_TRANS_5") (pin "A") (pinfunction "A_A") (pintype "bidirectional"))
      (node (ref "U$4") (pin "11") (pinfunction "11_11") (pintype "bidirectional"))
    )
    (net (code "14") (name "3_RX-") (class "Default")
      (node (ref "R10") (pin "1") (pinfunction "1_1") (pintype "passive"))
      (node (ref "RS_TRANS_5") (pin "B") (pinfunction "B_B") (pintype "bidirectional"))
      (node (ref "U$4") (pin "12") (pinfunction "12_12") (pintype "bidirectional"))
    )
    (net (code "15") (name "3_TX+") (class "Default")
      (node (ref "R12") (pin "1") (pinfunction "1_1") (pintype "passive"))
      (node (ref "RS_TRANS_5") (pin "Y") (pinfunction "Y_Y") (pintype "bidirectional"))
      (node (ref "U$4") (pin "9") (pinfunction "9_9") (pintype "bidirectional"))
    )
    (net (code "16") (name "3_TX-") (class "Default")
      (node (ref "R12") (pin "2") (pinfunction "2_2") (pintype "passive"))
      (node (ref "RS_TRANS_5") (pin "Z") (pinfunction "Z_Z") (pintype "bidirectional"))
      (node (ref "U$4") (pin "10") (pinfunction "10_10") (pintype "bidirectional"))
    )
    (net (code "17") (name "4_RX+") (class "Default")
      (node (ref "R14") (pin "2") (pinfunction "2_2") (pintype "passive"))
      (node (ref "RS_TRANS_7") (pin "A") (pinfunction "A_A") (pintype "bidirectional"))
      (node (ref "U$4") (pin "15") (pinfunction "15_15") (pintype "bidirectional"))
    )
    (net (code "18") (name "4_RX-") (class "Default")
      (node (ref "R14") (pin "1") (pinfunction "1_1") (pintype "passive"))
      (node (ref "RS_TRANS_7") (pin "B") (pinfunction "B_B") (pintype "bidirectional"))
      (node (ref "U$4") (pin "16") (pinfunction "16_16") (pintype "bidirectional"))
    )
    (net (code "19") (name "4_TX+") (class "Default")
      (node (ref "R16") (pin "1") (pinfunction "1_1") (pintype "passive"))
      (node (ref "RS_TRANS_7") (pin "Y") (pinfunction "Y_Y") (pintype "bidirectional"))
      (node (ref "U$4") (pin "13") (pinfunction "13_13") (pintype "bidirectional"))
    )
    (net (code "20") (name "4_TX-") (class "Default")
      (node (ref "R16") (pin "2") (pinfunction "2_2") (pintype "passive"))
      (node (ref "RS_TRANS_7") (pin "Z") (pinfunction "Z_Z") (pintype "bidirectional"))
      (node (ref "U$4") (pin "14") (pinfunction "14_14") (pintype "bidirectional"))
    )
    (net (code "21") (name "5_RX+") (class "Default")
      (node (ref "R18") (pin "2") (pinfunction "2_2") (pintype "passive"))
      (node (ref "RS_TRANS_9") (pin "A") (pinfunction "A_A") (pintype "bidirectional"))
      (node (ref "U$4") (pin "19") (pinfunction "19_19") (pintype "bidirectional"))
    )
    (net (code "22") (name "5_RX-") (class "Default")
      (node (ref "R18") (pin "1") (pinfunction "1_1") (pintype "passive"))
      (node (ref "RS_TRANS_9") (pin "B") (pinfunction "B_B") (pintype "bidirectional"))
      (node (ref "U$4") (pin "20") (pinfunction "20_20") (pintype "bidirectional"))
    )
    (net (code "23") (name "5_TX+") (class "Default")
      (node (ref "R20") (pin "1") (pinfunction "1_1") (pintype "passive"))
      (node (ref "RS_TRANS_9") (pin "Y") (pinfunction "Y_Y") (pintype "bidirectional"))
      (node (ref "U$4") (pin "17") (pinfunction "17_17") (pintype "bidirectional"))
    )
    (net (code "24") (name "5_TX-") (class "Default")
      (node (ref "R20") (pin "2") (pinfunction "2_2") (pintype "passive"))
      (node (ref "RS_TRANS_9") (pin "Z") (pinfunction "Z_Z") (pintype "bidirectional"))
      (node (ref "U$4") (pin "18") (pinfunction "18_18") (pintype "bidirectional"))
    )
    (net (code "25") (name "6_RX+") (class "Default")
      (node (ref "R22") (pin "2") (pinfunction "2_2") (pintype "passive"))
      (node (ref "RS_TRANS_11") (pin "A") (pinfunction "A_A") (pintype "bidirectional"))
      (node (ref "U$4") (pin "23") (pinfunction "23_23") (pintype "bidirectional"))
    )
    (net (code "26") (name "6_RX-") (class "Default")
      (node (ref "R22") (pin "1") (pinfunction "1_1") (pintype "passive"))
      (node (ref "RS_TRANS_11") (pin "B") (pinfunction "B_B") (pintype "bidirectional"))
      (node (ref "U$4") (pin "24") (pinfunction "24_24") (pintype "bidirectional"))
    )
    (net (code "27") (name "6_TX+") (class "Default")
      (node (ref "R24") (pin "1") (pinfunction "1_1") (pintype "passive"))
      (node (ref "RS_TRANS_11") (pin "Y") (pinfunction "Y_Y") (pintype "bidirectional"))
      (node (ref "U$4") (pin "21") (pinfunction "21_21") (pintype "bidirectional"))
    )
    (net (code "28") (name "6_TX-") (class "Default")
      (node (ref "R24") (pin "2") (pinfunction "2_2") (pintype "passive"))
      (node (ref "RS_TRANS_11") (pin "Z") (pinfunction "Z_Z") (pintype "bidirectional"))
      (node (ref "U$4") (pin "22") (pinfunction "22_22") (pintype "bidirectional"))
    )
    (net (code "29") (name "7_RX+") (class "Default")
      (node (ref "R3") (pin "2") (pinfunction "2_2") (pintype "passive"))
      (node (ref "RS_TRANS_2") (pin "A") (pinfunction "A_A") (pintype "bidirectional"))
      (node (ref "U$4") (pin "27") (pinfunction "27_27") (pintype "bidirectional"))
    )
    (net (code "30") (name "7_RX-") (class "Default")
      (node (ref "R3") (pin "1") (pinfunction "1_1") (pintype "passive"))
      (node (ref "RS_TRANS_2") (pin "B") (pinfunction "B_B") (pintype "bidirectional"))
      (node (ref "U$4") (pin "28") (pinfunction "28_28") (pintype "bidirectional"))
    )
    (net (code "31") (name "7_TX+") (class "Default")
      (node (ref "R5") (pin "1") (pinfunction "1_1") (pintype "passive"))
      (node (ref "RS_TRANS_2") (pin "Y") (pinfunction "Y_Y") (pintype "bidirectional"))
      (node (ref "U$4") (pin "25") (pinfunction "25_25") (pintype "bidirectional"))
    )
    (net (code "32") (name "7_TX-") (class "Default")
      (node (ref "R5") (pin "2") (pinfunction "2_2") (pintype "passive"))
      (node (ref "RS_TRANS_2") (pin "Z") (pinfunction "Z_Z") (pintype "bidirectional"))
      (node (ref "U$4") (pin "26") (pinfunction "26_26") (pintype "bidirectional"))
    )
    (net (code "33") (name "8_RX+") (class "Default")
      (node (ref "R7") (pin "2") (pinfunction "2_2") (pintype "passive"))
      (node (ref "RS_TRANS_4") (pin "A") (pinfunction "A_A") (pintype "bidirectional"))
      (node (ref "U$4") (pin "31") (pinfunction "31_31") (pintype "bidirectional"))
    )
    (net (code "34") (name "8_RX-") (class "Default")
      (node (ref "R7") (pin "1") (pinfunction "1_1") (pintype "passive"))
      (node (ref "RS_TRANS_4") (pin "B") (pinfunction "B_B") (pintype "bidirectional"))
      (node (ref "U$4") (pin "32") (pinfunction "32_32") (pintype "bidirectional"))
    )
    (net (code "35") (name "8_TX+") (class "Default")
      (node (ref "R9") (pin "1") (pinfunction "1_1") (pintype "passive"))
      (node (ref "RS_TRANS_4") (pin "Y") (pinfunction "Y_Y") (pintype "bidirectional"))
      (node (ref "U$4") (pin "29") (pinfunction "29_29") (pintype "bidirectional"))
    )
    (net (code "36") (name "8_TX-") (class "Default")
      (node (ref "R9") (pin "2") (pinfunction "2_2") (pintype "passive"))
      (node (ref "RS_TRANS_4") (pin "Z") (pinfunction "Z_Z") (pintype "bidirectional"))
      (node (ref "U$4") (pin "30") (pinfunction "30_30") (pintype "bidirectional"))
    )
    (net (code "37") (name "9_RX+") (class "Default")
      (node (ref "R11") (pin "2") (pinfunction "2_2") (pintype "passive"))
      (node (ref "RS_TRANS_6") (pin "A") (pinfunction "A_A") (pintype "bidirectional"))
      (node (ref "U$4") (pin "35") (pinfunction "35_35") (pintype "bidirectional"))
    )
    (net (code "38") (name "9_RX-") (class "Default")
      (node (ref "R11") (pin "1") (pinfunction "1_1") (pintype "passive"))
      (node (ref "RS_TRANS_6") (pin "B") (pinfunction "B_B") (pintype "bidirectional"))
      (node (ref "U$4") (pin "36") (pinfunction "36_36") (pintype "bidirectional"))
    )
    (net (code "39") (name "9_TX+") (class "Default")
      (node (ref "R13") (pin "1") (pinfunction "1_1") (pintype "passive"))
      (node (ref "RS_TRANS_6") (pin "Y") (pinfunction "Y_Y") (pintype "bidirectional"))
      (node (ref "U$4") (pin "33") (pinfunction "33_33") (pintype "bidirectional"))
    )
    (net (code "40") (name "9_TX-") (class "Default")
      (node (ref "R13") (pin "2") (pinfunction "2_2") (pintype "passive"))
      (node (ref "RS_TRANS_6") (pin "Z") (pinfunction "Z_Z") (pintype "bidirectional"))
      (node (ref "U$4") (pin "34") (pinfunction "34_34") (pintype "bidirectional"))
    )
    (net (code "41") (name "10_RX+") (class "Default")
      (node (ref "R15") (pin "2") (pinfunction "2_2") (pintype "passive"))
      (node (ref "RS_TRANS_8") (pin "A") (pinfunction "A_A") (pintype "bidirectional"))
      (node (ref "U$4") (pin "39") (pinfunction "39_39") (pintype "bidirectional"))
    )
    (net (code "42") (name "10_RX-") (class "Default")
      (node (ref "R15") (pin "1") (pinfunction "1_1") (pintype "passive"))
      (node (ref "RS_TRANS_8") (pin "B") (pinfunction "B_B") (pintype "bidirectional"))
      (node (ref "U$4") (pin "40") (pinfunction "40_40") (pintype "bidirectional"))
    )
    (net (code "43") (name "10_TX+") (class "Default")
      (node (ref "R17") (pin "1") (pinfunction "1_1") (pintype "passive"))
      (node (ref "RS_TRANS_8") (pin "Y") (pinfunction "Y_Y") (pintype "bidirectional"))
      (node (ref "U$4") (pin "37") (pinfunction "37_37") (pintype "bidirectional"))
    )
    (net (code "44") (name "10_TX-") (class "Default")
      (node (ref "R17") (pin "2") (pinfunction "2_2") (pintype "passive"))
      (node (ref "RS_TRANS_8") (pin "Z") (pinfunction "Z_Z") (pintype "bidirectional"))
      (node (ref "U$4") (pin "38") (pinfunction "38_38") (pintype "bidirectional"))
    )
    (net (code "45") (name "11_RX+") (class "Default")
      (node (ref "R19") (pin "2") (pinfunction "2_2") (pintype "passive"))
      (node (ref "RS_TRANS_10") (pin "A") (pinfunction "A_A") (pintype "bidirectional"))
      (node (ref "U$4") (pin "43") (pinfunction "43_43") (pintype "bidirectional"))
    )
    (net (code "46") (name "11_RX-") (class "Default")
      (node (ref "R19") (pin "1") (pinfunction "1_1") (pintype "passive"))
      (node (ref "RS_TRANS_10") (pin "B") (pinfunction "B_B") (pintype "bidirectional"))
      (node (ref "U$4") (pin "44") (pinfunction "44_44") (pintype "bidirectional"))
    )
    (net (code "47") (name "11_TX+") (class "Default")
      (node (ref "R21") (pin "1") (pinfunction "1_1") (pintype "passive"))
      (node (ref "RS_TRANS_10") (pin "Y") (pinfunction "Y_Y") (pintype "bidirectional"))
      (node (ref "U$4") (pin "41") (pinfunction "41_41") (pintype "bidirectional"))
    )
    (net (code "48") (name "11_TX-") (class "Default")
      (node (ref "R21") (pin "2") (pinfunction "2_2") (pintype "passive"))
      (node (ref "RS_TRANS_10") (pin "Z") (pinfunction "Z_Z") (pintype "bidirectional"))
      (node (ref "U$4") (pin "42") (pinfunction "42_42") (pintype "bidirectional"))
    )
    (net (code "49") (name "12_RX+") (class "Default")
      (node (ref "R23") (pin "2") (pinfunction "2_2") (pintype "passive"))
      (node (ref "RS_TRANS_12") (pin "A") (pinfunction "A_A") (pintype "bidirectional"))
      (node (ref "U$4") (pin "47") (pinfunction "47_47") (pintype "bidirectional"))
    )
    (net (code "50") (name "12_RX-") (class "Default")
      (node (ref "R23") (pin "1") (pinfunction "1_1") (pintype "passive"))
      (node (ref "RS_TRANS_12") (pin "B") (pinfunction "B_B") (pintype "bidirectional"))
      (node (ref "U$4") (pin "48") (pinfunction "48_48") (pintype "bidirectional"))
    )
    (net (code "51") (name "12_TX+") (class "Default")
      (node (ref "R25") (pin "1") (pinfunction "1_1") (pintype "passive"))
      (node (ref "RS_TRANS_12") (pin "Y") (pinfunction "Y_Y") (pintype "bidirectional"))
      (node (ref "U$4") (pin "45") (pinfunction "45_45") (pintype "bidirectional"))
    )
    (net (code "52") (name "12_TX-") (class "Default")
      (node (ref "R25") (pin "2") (pinfunction "2_2") (pintype "passive"))
      (node (ref "RS_TRANS_12") (pin "Z") (pinfunction "Z_Z") (pintype "bidirectional"))
      (node (ref "U$4") (pin "46") (pinfunction "46_46") (pintype "bidirectional"))
    )
    (net (code "53") (name "328_RX") (class "Default")
      (node (ref "U2") (pin "2") (pinfunction "PD0(RXD)_2") (pintype "bidirectional"))
      (node (ref "U5_MUX") (pin "4") (pinfunction "2Y3_4") (pintype "bidirectional"))
    )
    (net (code "54") (name "328_TX") (class "Default")
      (node (ref "U2") (pin "3") (pinfunction "PD1(TXD)_3") (pintype "bidirectional"))
      (node (ref "U5_MUX") (pin "11") (pinfunction "1Y3_11") (pintype "bidirectional"))
    )
    (net (code "55") (name "AT_MISO") (class "Default")
      (node (ref "J2") (pin "1") (pinfunction "1_1") (pintype "passive"))
      (node (ref "U2") (pin "18") (pinfunction "PB4(MISO)_18") (pintype "bidirectional"))
    )
    (net (code "56") (name "AT_MOSI") (class "Default")
      (node (ref "J2") (pin "4") (pinfunction "4_4") (pintype "passive"))
      (node (ref "U2") (pin "17") (pinfunction "PB3(MOSI/OC2)_17") (pintype "bidirectional"))
    )
    (net (code "57") (name "AT_SCK") (class "Default")
      (node (ref "J2") (pin "3") (pinfunction "3_3") (pintype "passive"))
      (node (ref "U2") (pin "19") (pinfunction "PB5(SCK)_19") (pintype "bidirectional"))
    )
    (net (code "58") (name "BLUETH_CTS") (class "Default")
      (node (ref "BLUETOOTH") (pin "CTS") (pinfunction "CTS_CTS") (pintype "bidirectional"))
      (node (ref "U2") (pin "13") (pinfunction "PD7(AIN1)_13") (pintype "bidirectional"))
    )
    (net (code "59") (name "BLUETH_RST") (class "Default")
      (node (ref "R42") (pin "1") (pinfunction "1_1") (pintype "passive"))
    )
    (net (code "60") (name "BLUETH_RTS") (class "Default")
      (node (ref "BLUETOOTH") (pin "RTS") (pinfunction "RTS_RTS") (pintype "bidirectional"))
      (node (ref "U2") (pin "12") (pinfunction "PD6(AIN0)_12") (pintype "bidirectional"))
    )
    (net (code "61") (name "BLUETH_RXD") (class "Default")
      (node (ref "BLUETOOTH") (pin "RXD") (pinfunction "RXD_RXD") (pintype "bidirectional"))
      (node (ref "U2") (pin "11") (pinfunction "PD5(T1)_11") (pintype "bidirectional"))
    )
    (net (code "62") (name "BLUETH_TXD") (class "Default")
      (node (ref "BLUETOOTH") (pin "TXD") (pinfunction "TXD_TXD") (pintype "bidirectional"))
      (node (ref "U2") (pin "6") (pinfunction "PD4(XCK/T0)_6") (pintype "bidirectional"))
    )
    (net (code "63") (name "GND") (class "Default")
      (node (ref "12V") (pin "1") (pinfunction "1_1") (pintype "passive"))
      (node (ref "5V") (pin "1") (pinfunction "1_1") (pintype "passive"))
      (node (ref "BLUETOOTH") (pin "GND") (pinfunction "GND_GND") (pintype "bidirectional"))
      (node (ref "C1") (pin "2") (pinfunction "2_2") (pintype "passive"))
      (node (ref "C10") (pin "2") (pinfunction "2_2") (pintype "passive"))
      (node (ref "C11") (pin "2") (pinfunction "2_2") (pintype "passive"))
      (node (ref "C12") (pin "2") (pinfunction "2_2") (pintype "passive"))
      (node (ref "C13") (pin "2") (pinfunction "2_2") (pintype "passive"))
      (node (ref "C14") (pin "2") (pinfunction "2_2") (pintype "passive"))
      (node (ref "C15") (pin "2") (pinfunction "2_2") (pintype "passive"))
      (node (ref "C16") (pin "2") (pinfunction "2_2") (pintype "passive"))
      (node (ref "C17") (pin "2") (pinfunction "2_2") (pintype "passive"))
      (node (ref "C18") (pin "2") (pinfunction "2_2") (pintype "passive"))
      (node (ref "C19") (pin "2") (pinfunction "2_2") (pintype "passive"))
      (node (ref "C2") (pin "2") (pinfunction "2_2") (pintype "passive"))
      (node (ref "C20") (pin "2") (pinfunction "2_2") (pintype "passive"))
      (node (ref "C21") (pin "2") (pinfunction "2_2") (pintype "passive"))
      (node (ref "C22") (pin "2") (pinfunction "2_2") (pintype "passive"))
      (node (ref "C23") (pin "2") (pinfunction "2_2") (pintype "passive"))
      (node (ref "C24") (pin "2") (pinfunction "2_2") (pintype "passive"))
      (node (ref "C25") (pin "2") (pinfunction "2_2") (pintype "passive"))
      (node (ref "C26") (pin "2") (pinfunction "2_2") (pintype "passive"))
      (node (ref "C27") (pin "2") (pinfunction "2_2") (pintype "passive"))
      (node (ref "C28") (pin "2") (pinfunction "2_2") (pintype "passive"))
      (node (ref "C29") (pin "2") (pinfunction "2_2") (pintype "passive"))
      (node (ref "C3") (pin "2") (pinfunction "2_2") (pintype "passive"))
      (node (ref "C30") (pin "2") (pinfunction "2_2") (pintype "passive"))
      (node (ref "C31") (pin "2") (pinfunction "2_2") (pintype "passive"))
      (node (ref "C32") (pin "2") (pinfunction "2_2") (pintype "passive"))
      (node (ref "C33") (pin "1") (pinfunction "1_1") (pintype "passive"))
      (node (ref "C34") (pin "2") (pinfunction "2_2") (pintype "passive"))
      (node (ref "C4") (pin "2") (pinfunction "2_2") (pintype "passive"))
      (node (ref "C5") (pin "2") (pinfunction "2_2") (pintype "passive"))
      (node (ref "C6") (pin "2") (pinfunction "2_2") (pintype "passive"))
      (node (ref "C7") (pin "2") (pinfunction "2_2") (pintype "passive"))
      (node (ref "C8") (pin "2") (pinfunction "2_2") (pintype "passive"))
      (node (ref "C9") (pin "2") (pinfunction "2_2") (pintype "passive"))
      (node (ref "D1") (pin "C") (pinfunction "C_C") (pintype "passive"))
      (node (ref "FAN1") (pin "1") (pinfunction "1_1") (pintype "passive"))
      (node (ref "FAN2") (pin "1") (pinfunction "1_1") (pintype "passive"))
      (node (ref "FAN3") (pin "1") (pinfunction "1_1") (pintype "passive"))
      (node (ref "FAN4") (pin "1") (pinfunction "1_1") (pintype "passive"))
      (node (ref "GPS") (pin "P$12") (pinfunction "GND_P$12") (pintype "bidirectional"))
      (node (ref "GPS") (pin "P$19") (pinfunction "GND_P$19") (pintype "bidirectional"))
      (node (ref "GPS") (pin "P$3") (pinfunction "GND_P$3") (pintype "bidirectional"))
      (node (ref "GPS") (pin "P$8") (pinfunction "GND_P$8") (pintype "bidirectional"))
      (node (ref "J1") (pin "P$1") (pinfunction "GND_P$1") (pintype "bidirectional"))
      (node (ref "J1") (pin "P$2") (pinfunction "GND_P$2") (pintype "bidirectional"))
      (node (ref "J2") (pin "6") (pinfunction "6_6") (pintype "passive"))
      (node (ref "LCD") (pin "1") (pinfunction "1_1") (pintype "passive"))
      (node (ref "LCD") (pin "16") (pinfunction "16_16") (pintype "passive"))
      (node (ref "LCD") (pin "5") (pinfunction "5_5") (pintype "passive"))
      (node (ref "R40") (pin "1") (pinfunction "1_1") (pintype "passive"))
      (node (ref "RS-485-1") (pin "GND") (pinfunction "GND_GND") (pintype "bidirectional"))
      (node (ref "RS-485-2") (pin "GND") (pinfunction "GND_GND") (pintype "bidirectional"))
      (node (ref "RS-485-3") (pin "GND") (pinfunction "GND_GND") (pintype "bidirectional"))
      (node (ref "RS-485-4") (pin "GND") (pinfunction "GND_GND") (pintype "bidirectional"))
      (node (ref "RS-485-5") (pin "GND") (pinfunction "GND_GND") (pintype "bidirectional"))
      (node (ref "RS-485-6") (pin "GND") (pinfunction "GND_GND") (pintype "bidirectional"))
      (node (ref "RS_TRANS_1") (pin "GND") (pinfunction "GND_GND") (pintype "bidirectional"))
      (node (ref "RS_TRANS_10") (pin "GND") (pinfunction "GND_GND") (pintype "bidirectional"))
      (node (ref "RS_TRANS_11") (pin "GND") (pinfunction "GND_GND") (pintype "bidirectional"))
      (node (ref "RS_TRANS_12") (pin "GND") (pinfunction "GND_GND") (pintype "bidirectional"))
      (node (ref "RS_TRANS_2") (pin "GND") (pinfunction "GND_GND") (pintype "bidirectional"))
      (node (ref "RS_TRANS_3") (pin "GND") (pinfunction "GND_GND") (pintype "bidirectional"))
      (node (ref "RS_TRANS_4") (pin "GND") (pinfunction "GND_GND") (pintype "bidirectional"))
      (node (ref "RS_TRANS_5") (pin "GND") (pinfunction "GND_GND") (pintype "bidirectional"))
      (node (ref "RS_TRANS_6") (pin "GND") (pinfunction "GND_GND") (pintype "bidirectional"))
      (node (ref "RS_TRANS_7") (pin "GND") (pinfunction "GND_GND") (pintype "bidirectional"))
      (node (ref "RS_TRANS_8") (pin "GND") (pinfunction "GND_GND") (pintype "bidirectional"))
      (node (ref "RS_TRANS_9") (pin "GND") (pinfunction "GND_GND") (pintype "bidirectional"))
      (node (ref "TEMP") (pin "3") (pinfunction "3_3") (pintype "passive"))
      (node (ref "U$1") (pin "GND") (pinfunction "GND_GND") (pintype "bidirectional"))
      (node (ref "U$2") (pin "P$1") (pinfunction "E_P$1") (pintype "passive"))
      (node (ref "U$3") (pin "GND1") (pinfunction "GND1_GND1") (pintype "bidirectional"))
      (node (ref "U$3") (pin "GND2") (pinfunction "GND2_GND2") (pintype "power_in"))
      (node (ref "U1") (pin "11") (pinfunction "GND_11") (pintype "bidirectional"))
      (node (ref "U1") (pin "29") (pinfunction "GND_29") (pintype "bidirectional"))
      (node (ref "U1") (pin "30") (pinfunction "GND_30") (pintype "bidirectional"))
      (node (ref "U1") (pin "39") (pinfunction "GND_39") (pintype "bidirectional"))
      (node (ref "U1") (pin "40") (pinfunction "GND_40") (pintype "bidirectional"))
      (node (ref "U1_MUX") (pin "6") (pinfunction "~{E}_6") (pintype "input"))
      (node (ref "U1_MUX") (pin "7") (pinfunction "VEE_7") (pintype "power_in"))
      (node (ref "U1_MUX") (pin "8") (pinfunction "GND_8") (pintype "passive"))
      (node (ref "U2") (pin "22") (pinfunction "GND_22") (pintype "bidirectional"))
      (node (ref "U2") (pin "8") (pinfunction "GND_8") (pintype "bidirectional"))
      (node (ref "U2_MUX") (pin "6") (pinfunction "~{E}_6") (pintype "input"))
      (node (ref "U2_MUX") (pin "7") (pinfunction "VEE_7") (pintype "power_in"))
      (node (ref "U2_MUX") (pin "8") (pinfunction "GND_8") (pintype "passive"))
      (node (ref "U3_MUX") (pin "6") (pinfunction "~{E}_6") (pintype "input"))
      (node (ref "U3_MUX") (pin "7") (pinfunction "VEE_7") (pintype "power_in"))
      (node (ref "U3_MUX") (pin "8") (pinfunction "GND_8") (pintype "passive"))
      (node (ref "U4_MUX") (pin "6") (pinfunction "~{E}_6") (pintype "input"))
      (node (ref "U4_MUX") (pin "7") (pinfunction "VEE_7") (pintype "power_in"))
      (node (ref "U4_MUX") (pin "8") (pinfunction "GND_8") (pintype "passive"))
      (node (ref "U5_MUX") (pin "6") (pinfunction "~{E}_6") (pintype "input"))
      (node (ref "U5_MUX") (pin "7") (pinfunction "VEE_7") (pintype "power_in"))
      (node (ref "U5_MUX") (pin "8") (pinfunction "GND_8") (pintype "passive"))
      (node (ref "U7_MUX") (pin "6") (pinfunction "~{E}_6") (pintype "input"))
      (node (ref "U7_MUX") (pin "7") (pinfunction "VEE_7") (pintype "power_in"))
      (node (ref "U7_MUX") (pin "8") (pinfunction "GND_8") (pintype "passive"))
    )
    (net (code "64") (name "GPS_RX") (class "Default")
      (node (ref "D3") (pin "C") (pinfunction "C_C") (pintype "passive"))
      (node (ref "U2") (pin "4") (pinfunction "PD2(INT0)_4") (pintype "bidirectional"))
    )
    (net (code "65") (name "GPS_TX") (class "Default")
      (node (ref "GPS") (pin "P$9") (pinfunction "TX_P$9") (pintype "bidirectional"))
      (node (ref "U2") (pin "5") (pinfunction "PD3(INT1)_5") (pintype "bidirectional"))
    )
    (net (code "66") (name "LCD_D4") (class "Default")
      (node (ref "LCD") (pin "11") (pinfunction "11_11") (pintype "passive"))
      (node (ref "U$3") (pin "PF1") (pinfunction "PF1_PF1") (pintype "bidirectional"))
    )
    (net (code "67") (name "LCD_D5") (class "Default")
      (node (ref "LCD") (pin "12") (pinfunction "12_12") (pintype "passive"))
      (node (ref "U$3") (pin "PF2") (pinfunction "PF2_PF2") (pintype "bidirectional"))
    )
    (net (code "68") (name "LCD_D6") (class "Default")
      (node (ref "LCD") (pin "13") (pinfunction "13_13") (pintype "passive"))
      (node (ref "U$3") (pin "PF3") (pinfunction "PF3_PF3") (pintype "bidirectional"))
    )
    (net (code "69") (name "LCD_D7") (class "Default")
      (node (ref "LCD") (pin "14") (pinfunction "14_14") (pintype "passive"))
      (node (ref "U$3") (pin "PF4") (pinfunction "PF4_PF4") (pintype "bidirectional"))
    )
    (net (code "70") (name "LCD_EN") (class "Default")
      (node (ref "LCD") (pin "6") (pinfunction "6_6") (pintype "passive"))
      (node (ref "U$3") (pin "PF0") (pinfunction "PF0_PF0") (pintype "bidirectional"))
    )
    (net (code "71") (name "LCD_RS") (class "Default")
      (node (ref "LCD") (pin "4") (pinfunction "4_4") (pintype "passive"))
      (node (ref "U$3") (pin "PD3") (pinfunction "PD3_PD3") (pintype "bidirectional"))
    )
    (net (code "72") (name "Net-(BLUETOOTH-PadRESET)") (class "Default")
      (node (ref "BLUETOOTH") (pin "RESET") (pinfunction "RESET_RESET") (pintype "bidirectional"))
      (node (ref "C34") (pin "1") (pinfunction "1_1") (pintype "passive"))
      (node (ref "R42") (pin "2") (pinfunction "2_2") (pintype "passive"))
    )
    (net (code "73") (name "Net-(D1-PadA)") (class "Default")
      (node (ref "D1") (pin "A") (pinfunction "A_A") (pintype "passive"))
      (node (ref "R1") (pin "2") (pinfunction "2_2") (pintype "passive"))
    )
    (net (code "74") (name "Net-(D2-PadC)") (class "Default")
      (node (ref "D2") (pin "C") (pinfunction "C_C") (pintype "passive"))
      (node (ref "R40") (pin "2") (pinfunction "2_2") (pintype "passive"))
    )
    (net (code "75") (name "Net-(GPS-3D-FIX)") (class "Default")
      (node (ref "D2") (pin "A") (pinfunction "A_A") (pintype "passive"))
      (node (ref "GPS") (pin "P$5") (pinfunction "3D-FIX_P$5") (pintype "bidirectional"))
    )
    (net (code "76") (name "Net-(GPS-EX_ANT)") (class "Default")
      (node (ref "GPS") (pin "P$11") (pinfunction "EX_ANT_P$11") (pintype "bidirectional"))
      (node (ref "J1") (pin "P$3") (pinfunction "SIGNAL_P$3") (pintype "bidirectional"))
    )
    (net (code "77") (name "Net-(GPS-RX)") (class "Default")
      (node (ref "D3") (pin "A") (pinfunction "A_A") (pintype "passive"))
      (node (ref "GPS") (pin "P$10") (pinfunction "RX_P$10") (pintype "bidirectional"))
      (node (ref "R41") (pin "1") (pinfunction "1_1") (pintype "passive"))
    )
    (net (code "78") (name "Net-(GPS-VCC)") (class "Default")
      (node (ref "C27") (pin "1") (pinfunction "1_1") (pintype "passive"))
      (node (ref "C28") (pin "1") (pinfunction "1_1") (pintype "passive"))
      (node (ref "GPS") (pin "P$1") (pinfunction "VCC_P$1") (pintype "bidirectional"))
      (node (ref "L1") (pin "2") (pinfunction "2_2") (pintype "passive"))
    )
    (net (code "79") (name "Net-(R26-Pad1)") (class "Default")
      (node (ref "R26") (pin "1") (pinfunction "1_1") (pintype "passive"))
      (node (ref "RS-485-1") (pin "A") (pinfunction "A_A") (pintype "bidirectional"))
      (node (ref "U$5") (pin "1") (pinfunction "1_1") (pintype "bidirectional"))
    )
    (net (code "80") (name "Net-(R26-Pad2)") (class "Default")
      (node (ref "R26") (pin "2") (pinfunction "2_2") (pintype "passive"))
      (node (ref "RS-485-1") (pin "B") (pinfunction "B_B") (pintype "bidirectional"))
      (node (ref "U$5") (pin "2") (pinfunction "2_2") (pintype "bidirectional"))
    )
    (net (code "81") (name "Net-(R27-Pad1)") (class "Default")
      (node (ref "R27") (pin "1") (pinfunction "1_1") (pintype "passive"))
      (node (ref "RS-485-2") (pin "A") (pinfunction "A_A") (pintype "bidirectional"))
      (node (ref "U$6") (pin "1") (pinfunction "1_1") (pintype "bidirectional"))
    )
    (net (code "82") (name "Net-(R27-Pad2)") (class "Default")
      (node (ref "R27") (pin "2") (pinfunction "2_2") (pintype "passive"))
      (node (ref "RS-485-2") (pin "B") (pinfunction "B_B") (pintype "bidirectional"))
      (node (ref "U$6") (pin "2") (pinfunction "2_2") (pintype "bidirectional"))
    )
    (net (code "83") (name "Net-(R28-Pad1)") (class "Default")
      (node (ref "R28") (pin "1") (pinfunction "1_1") (pintype "passive"))
      (node (ref "RS-485-1") (pin "Y") (pinfunction "Y_Y") (pintype "bidirectional"))
      (node (ref "U$5") (pin "3") (pinfunction "3_3") (pintype "bidirectional"))
    )
    (net (code "84") (name "Net-(R28-Pad2)") (class "Default")
      (node (ref "R28") (pin "2") (pinfunction "2_2") (pintype "passive"))
      (node (ref "RS-485-1") (pin "Z") (pinfunction "Z_Z") (pintype "bidirectional"))
      (node (ref "U$5") (pin "6") (pinfunction "6_6") (pintype "bidirectional"))
    )
    (net (code "85") (name "Net-(R29-Pad1)") (class "Default")
      (node (ref "R29") (pin "1") (pinfunction "1_1") (pintype "passive"))
      (node (ref "RS-485-2") (pin "Y") (pinfunction "Y_Y") (pintype "bidirectional"))
      (node (ref "U$6") (pin "3") (pinfunction "3_3") (pintype "bidirectional"))
    )
    (net (code "86") (name "Net-(R29-Pad2)") (class "Default")
      (node (ref "R29") (pin "2") (pinfunction "2_2") (pintype "passive"))
      (node (ref "RS-485-2") (pin "Z") (pinfunction "Z_Z") (pintype "bidirectional"))
      (node (ref "U$6") (pin "6") (pinfunction "6_6") (pintype "bidirectional"))
    )
    (net (code "87") (name "Net-(R30-Pad1)") (class "Default")
      (node (ref "R30") (pin "1") (pinfunction "1_1") (pintype "passive"))
      (node (ref "RS-485-3") (pin "A") (pinfunction "A_A") (pintype "bidirectional"))
      (node (ref "U$7") (pin "1") (pinfunction "1_1") (pintype "bidirectional"))
    )
    (net (code "88") (name "Net-(R30-Pad2)") (class "Default")
      (node (ref "R30") (pin "2") (pinfunction "2_2") (pintype "passive"))
      (node (ref "RS-485-3") (pin "B") (pinfunction "B_B") (pintype "bidirectional"))
      (node (ref "U$7") (pin "2") (pinfunction "2_2") (pintype "bidirectional"))
    )
    (net (code "89") (name "Net-(R31-Pad1)") (class "Default")
      (node (ref "R31") (pin "1") (pinfunction "1_1") (pintype "passive"))
      (node (ref "RS-485-4") (pin "A") (pinfunction "A_A") (pintype "bidirectional"))
      (node (ref "U$8") (pin "1") (pinfunction "1_1") (pintype "bidirectional"))
    )
    (net (code "90") (name "Net-(R31-Pad2)") (class "Default")
      (node (ref "R31") (pin "2") (pinfunction "2_2") (pintype "passive"))
      (node (ref "RS-485-4") (pin "B") (pinfunction "B_B") (pintype "bidirectional"))
      (node (ref "U$8") (pin "2") (pinfunction "2_2") (pintype "bidirectional"))
    )
    (net (code "91") (name "Net-(R32-Pad1)") (class "Default")
      (node (ref "R32") (pin "1") (pinfunction "1_1") (pintype "passive"))
      (node (ref "RS-485-3") (pin "Y") (pinfunction "Y_Y") (pintype "bidirectional"))
      (node (ref "U$7") (pin "3") (pinfunction "3_3") (pintype "bidirectional"))
    )
    (net (code "92") (name "Net-(R32-Pad2)") (class "Default")
      (node (ref "R32") (pin "2") (pinfunction "2_2") (pintype "passive"))
      (node (ref "RS-485-3") (pin "Z") (pinfunction "Z_Z") (pintype "bidirectional"))
      (node (ref "U$7") (pin "6") (pinfunction "6_6") (pintype "bidirectional"))
    )
    (net (code "93") (name "Net-(R33-Pad1)") (class "Default")
      (node (ref "R33") (pin "1") (pinfunction "1_1") (pintype "passive"))
      (node (ref "RS-485-4") (pin "Y") (pinfunction "Y_Y") (pintype "bidirectional"))
      (node (ref "U$8") (pin "3") (pinfunction "3_3") (pintype "bidirectional"))
    )
    (net (code "94") (name "Net-(R33-Pad2)") (class "Default")
      (node (ref "R33") (pin "2") (pinfunction "2_2") (pintype "passive"))
      (node (ref "RS-485-4") (pin "Z") (pinfunction "Z_Z") (pintype "bidirectional"))
      (node (ref "U$8") (pin "6") (pinfunction "6_6") (pintype "bidirectional"))
    )
    (net (code "95") (name "Net-(R34-Pad1)") (class "Default")
      (node (ref "R34") (pin "1") (pinfunction "1_1") (pintype "passive"))
      (node (ref "RS-485-5") (pin "A") (pinfunction "A_A") (pintype "bidirectional"))
      (node (ref "U$9") (pin "1") (pinfunction "1_1") (pintype "bidirectional"))
    )
    (net (code "96") (name "Net-(R34-Pad2)") (class "Default")
      (node (ref "R34") (pin "2") (pinfunction "2_2") (pintype "passive"))
      (node (ref "RS-485-5") (pin "B") (pinfunction "B_B") (pintype "bidirectional"))
      (node (ref "U$9") (pin "2") (pinfunction "2_2") (pintype "bidirectional"))
    )
    (net (code "97") (name "Net-(R35-Pad1)") (class "Default")
      (node (ref "R35") (pin "1") (pinfunction "1_1") (pintype "passive"))
      (node (ref "RS-485-5") (pin "Y") (pinfunction "Y_Y") (pintype "bidirectional"))
      (node (ref "U$9") (pin "3") (pinfunction "3_3") (pintype "bidirectional"))
    )
    (net (code "98") (name "Net-(R35-Pad2)") (class "Default")
      (node (ref "R35") (pin "2") (pinfunction "2_2") (pintype "passive"))
      (node (ref "RS-485-5") (pin "Z") (pinfunction "Z_Z") (pintype "bidirectional"))
      (node (ref "U$9") (pin "6") (pinfunction "6_6") (pintype "bidirectional"))
    )
    (net (code "99") (name "Net-(R36-Pad1)") (class "Default")
      (node (ref "R36") (pin "1") (pinfunction "1_1") (pintype "passive"))
      (node (ref "RS-485-6") (pin "A") (pinfunction "A_A") (pintype "bidirectional"))
      (node (ref "U$10") (pin "1") (pinfunction "1_1") (pintype "bidirectional"))
    )
    (net (code "100") (name "Net-(R36-Pad2)") (class "Default")
      (node (ref "R36") (pin "2") (pinfunction "2_2") (pintype "passive"))
      (node (ref "RS-485-6") (pin "B") (pinfunction "B_B") (pintype "bidirectional"))
      (node (ref "U$10") (pin "2") (pinfunction "2_2") (pintype "bidirectional"))
    )
    (net (code "101") (name "Net-(R37-Pad1)") (class "Default")
      (node (ref "R37") (pin "1") (pinfunction "1_1") (pintype "passive"))
      (node (ref "RS-485-6") (pin "Y") (pinfunction "Y_Y") (pintype "bidirectional"))
      (node (ref "U$10") (pin "3") (pinfunction "3_3") (pintype "bidirectional"))
    )
    (net (code "102") (name "Net-(R37-Pad2)") (class "Default")
      (node (ref "R37") (pin "2") (pinfunction "2_2") (pintype "passive"))
      (node (ref "RS-485-6") (pin "Z") (pinfunction "Z_Z") (pintype "bidirectional"))
      (node (ref "U$10") (pin "6") (pinfunction "6_6") (pintype "bidirectional"))
    )
    (net (code "103") (name "Net-(S1-S)") (class "Default")
      (node (ref "S1") (pin "3") (pinfunction "S_3") (pintype "passive"))
      (node (ref "U$3") (pin "VBUS") (pinfunction "VBUS_VBUS") (pintype "power_in"))
    )
    (net (code "104") (name "Net-(U$2-S)") (class "Default")
      (node (ref "LCD") (pin "3") (pinfunction "3_3") (pintype "passive"))
      (node (ref "U$2") (pin "P$2") (pinfunction "S_P$2") (pintype "passive"))
    )
    (net (code "105") (name "Net-(U2-PB6(XTAL1{slash}TOSC1))") (class "Default")
      (node (ref "C31") (pin "1") (pinfunction "1_1") (pintype "passive"))
      (node (ref "U2") (pin "9") (pinfunction "PB6(XTAL1/TOSC1)_9") (pintype "bidirectional"))
      (node (ref "Y1") (pin "2") (pinfunction "2_2") (pintype "passive"))
    )
    (net (code "106") (name "Net-(U2-PB7(XTAL2{slash}TOSC2))") (class "Default")
      (node (ref "C32") (pin "1") (pinfunction "1_1") (pintype "passive"))
      (node (ref "U2") (pin "10") (pinfunction "PB7(XTAL2/TOSC2)_10") (pintype "bidirectional"))
      (node (ref "Y1") (pin "1") (pinfunction "1_1") (pintype "passive"))
    )
    (net (code "107") (name "RESET") (class "Default")
      (node (ref "J2") (pin "5") (pinfunction "5_5") (pintype "passive"))
      (node (ref "R39") (pin "1") (pinfunction "1_1") (pintype "passive"))
      (node (ref "U$3") (pin "RST") (pinfunction "RST_RST") (pintype "power_in"))
      (node (ref "U1") (pin "22") (pinfunction "/RESET_22") (pintype "bidirectional"))
      (node (ref "U2") (pin "1") (pinfunction "PC6(/RESET)_1") (pintype "bidirectional"))
    )
    (net (code "108") (name "RS485_1_RX") (class "Default")
      (node (ref "RS_TRANS_1") (pin "RO") (pinfunction "R0_RO") (pintype "bidirectional"))
      (node (ref "U1_MUX") (pin "12") (pinfunction "1Y0_12") (pintype "bidirectional"))
    )
    (net (code "109") (name "RS485_1_TX") (class "Default")
      (node (ref "RS_TRANS_1") (pin "DI") (pinfunction "DI_DI") (pintype "bidirectional"))
      (node (ref "U1_MUX") (pin "1") (pinfunction "2Y0_1") (pintype "bidirectional"))
    )
    (net (code "110") (name "RS485_2_RX") (class "Default")
      (node (ref "RS_TRANS_3") (pin "RO") (pinfunction "R0_RO") (pintype "bidirectional"))
      (node (ref "U2_MUX") (pin "12") (pinfunction "1Y0_12") (pintype "bidirectional"))
    )
    (net (code "111") (name "RS485_2_TX") (class "Default")
      (node (ref "RS_TRANS_3") (pin "DI") (pinfunction "DI_DI") (pintype "bidirectional"))
      (node (ref "U2_MUX") (pin "1") (pinfunction "2Y0_1") (pintype "bidirectional"))
    )
    (net (code "112") (name "RS485_3_RX") (class "Default")
      (node (ref "RS_TRANS_5") (pin "RO") (pinfunction "R0_RO") (pintype "bidirectional"))
      (node (ref "U3_MUX") (pin "12") (pinfunction "1Y0_12") (pintype "bidirectional"))
    )
    (net (code "113") (name "RS485_3_TX") (class "Default")
      (node (ref "RS_TRANS_5") (pin "DI") (pinfunction "DI_DI") (pintype "bidirectional"))
      (node (ref "U3_MUX") (pin "1") (pinfunction "2Y0_1") (pintype "bidirectional"))
    )
    (net (code "114") (name "RS485_4_RX") (class "Default")
      (node (ref "RS_TRANS_7") (pin "RO") (pinfunction "R0_RO") (pintype "bidirectional"))
      (node (ref "U4_MUX") (pin "12") (pinfunction "1Y0_12") (pintype "bidirectional"))
    )
    (net (code "115") (name "RS485_4_TX") (class "Default")
      (node (ref "RS_TRANS_7") (pin "DI") (pinfunction "DI_DI") (pintype "bidirectional"))
      (node (ref "U4_MUX") (pin "1") (pinfunction "2Y0_1") (pintype "bidirectional"))
    )
    (net (code "116") (name "RS485_5_RX") (class "Default")
      (node (ref "RS_TRANS_9") (pin "RO") (pinfunction "R0_RO") (pintype "bidirectional"))
      (node (ref "U4_MUX") (pin "14") (pinfunction "1Y1_14") (pintype "bidirectional"))
    )
    (net (code "117") (name "RS485_5_TX") (class "Default")
      (node (ref "RS_TRANS_9") (pin "DI") (pinfunction "DI_DI") (pintype "bidirectional"))
      (node (ref "U4_MUX") (pin "5") (pinfunction "2Y1_5") (pintype "bidirectional"))
    )
    (net (code "118") (name "RS485_6_RX") (class "Default")
      (node (ref "RS_TRANS_11") (pin "RO") (pinfunction "R0_RO") (pintype "bidirectional"))
      (node (ref "U3_MUX") (pin "14") (pinfunction "1Y1_14") (pintype "bidirectional"))
    )
    (net (code "119") (name "RS485_6_TX") (class "Default")
      (node (ref "RS_TRANS_11") (pin "DI") (pinfunction "DI_DI") (pintype "bidirectional"))
      (node (ref "U3_MUX") (pin "5") (pinfunction "2Y1_5") (pintype "bidirectional"))
    )
    (net (code "120") (name "RS485_7_RX") (class "Default")
      (node (ref "RS_TRANS_2") (pin "RO") (pinfunction "R0_RO") (pintype "bidirectional"))
      (node (ref "U2_MUX") (pin "14") (pinfunction "1Y1_14") (pintype "bidirectional"))
    )
    (net (code "121") (name "RS485_7_TX") (class "Default")
      (node (ref "RS_TRANS_2") (pin "DI") (pinfunction "DI_DI") (pintype "bidirectional"))
      (node (ref "U2_MUX") (pin "5") (pinfunction "2Y1_5") (pintype "bidirectional"))
    )
    (net (code "122") (name "RS485_8_RX") (class "Default")
      (node (ref "RS_TRANS_4") (pin "RO") (pinfunction "R0_RO") (pintype "bidirectional"))
      (node (ref "U1_MUX") (pin "14") (pinfunction "1Y1_14") (pintype "bidirectional"))
    )
    (net (code "123") (name "RS485_8_TX") (class "Default")
      (node (ref "RS_TRANS_4") (pin "DI") (pinfunction "DI_DI") (pintype "bidirectional"))
      (node (ref "U1_MUX") (pin "5") (pinfunction "2Y1_5") (pintype "bidirectional"))
    )
    (net (code "124") (name "RS485_9_RX") (class "Default")
      (node (ref "RS_TRANS_6") (pin "RO") (pinfunction "R0_RO") (pintype "bidirectional"))
      (node (ref "U1_MUX") (pin "15") (pinfunction "1Y2_15") (pintype "bidirectional"))
    )
    (net (code "125") (name "RS485_9_TX") (class "Default")
      (node (ref "RS_TRANS_6") (pin "DI") (pinfunction "DI_DI") (pintype "bidirectional"))
      (node (ref "U1_MUX") (pin "2") (pinfunction "2Y2_2") (pintype "bidirectional"))
    )
    (net (code "126") (name "RS485_10_RX") (class "Default")
      (node (ref "RS_TRANS_8") (pin "RO") (pinfunction "R0_RO") (pintype "bidirectional"))
      (node (ref "U2_MUX") (pin "15") (pinfunction "1Y2_15") (pintype "bidirectional"))
    )
    (net (code "127") (name "RS485_10_TX") (class "Default")
      (node (ref "RS_TRANS_8") (pin "DI") (pinfunction "DI_DI") (pintype "bidirectional"))
      (node (ref "U2_MUX") (pin "2") (pinfunction "2Y2_2") (pintype "bidirectional"))
    )
    (net (code "128") (name "RS485_11_RX") (class "Default")
      (node (ref "RS_TRANS_10") (pin "RO") (pinfunction "R0_RO") (pintype "bidirectional"))
      (node (ref "U3_MUX") (pin "15") (pinfunction "1Y2_15") (pintype "bidirectional"))
    )
    (net (code "129") (name "RS485_11_TX") (class "Default")
      (node (ref "RS_TRANS_10") (pin "DI") (pinfunction "DI_DI") (pintype "bidirectional"))
      (node (ref "U3_MUX") (pin "2") (pinfunction "2Y2_2") (pintype "bidirectional"))
    )
    (net (code "130") (name "RS485_12_RX") (class "Default")
      (node (ref "RS_TRANS_12") (pin "RO") (pinfunction "R0_RO") (pintype "bidirectional"))
      (node (ref "U4_MUX") (pin "15") (pinfunction "1Y2_15") (pintype "bidirectional"))
    )
    (net (code "131") (name "RS485_12_TX") (class "Default")
      (node (ref "RS_TRANS_12") (pin "DI") (pinfunction "DI_DI") (pintype "bidirectional"))
      (node (ref "U4_MUX") (pin "2") (pinfunction "2Y2_2") (pintype "bidirectional"))
    )
    (net (code "132") (name "RS485_13_RX") (class "Default")
      (node (ref "RS-485-1") (pin "RO") (pinfunction "R0_RO") (pintype "bidirectional"))
      (node (ref "U5_MUX") (pin "12") (pinfunction "1Y0_12") (pintype "bidirectional"))
    )
    (net (code "133") (name "RS485_13_TX") (class "Default")
      (node (ref "RS-485-1") (pin "DI") (pinfunction "DI_DI") (pintype "bidirectional"))
      (node (ref "U5_MUX") (pin "1") (pinfunction "2Y0_1") (pintype "bidirectional"))
    )
    (net (code "134") (name "RS485_14_RX") (class "Default")
      (node (ref "RS-485-3") (pin "RO") (pinfunction "R0_RO") (pintype "bidirectional"))
      (node (ref "U5_MUX") (pin "14") (pinfunction "1Y1_14") (pintype "bidirectional"))
    )
    (net (code "135") (name "RS485_14_TX") (class "Default")
      (node (ref "RS-485-3") (pin "DI") (pinfunction "DI_DI") (pintype "bidirectional"))
      (node (ref "U5_MUX") (pin "5") (pinfunction "2Y1_5") (pintype "bidirectional"))
    )
    (net (code "136") (name "RS485_15_RX") (class "Default")
      (node (ref "RS-485-5") (pin "RO") (pinfunction "R0_RO") (pintype "bidirectional"))
      (node (ref "U5_MUX") (pin "15") (pinfunction "1Y2_15") (pintype "bidirectional"))
    )
    (net (code "137") (name "RS485_15_TX") (class "Default")
      (node (ref "RS-485-5") (pin "DI") (pinfunction "DI_DI") (pintype "bidirectional"))
      (node (ref "U5_MUX") (pin "2") (pinfunction "2Y2_2") (pintype "bidirectional"))
    )
    (net (code "138") (name "RS485_16_RX") (class "Default")
      (node (ref "RS-485-6") (pin "RO") (pinfunction "R0_RO") (pintype "bidirectional"))
      (node (ref "U7_MUX") (pin "12") (pinfunction "1Y0_12") (pintype "bidirectional"))
    )
    (net (code "139") (name "RS485_16_TX") (class "Default")
      (node (ref "RS-485-6") (pin "DI") (pinfunction "DI_DI") (pintype "bidirectional"))
      (node (ref "U7_MUX") (pin "1") (pinfunction "2Y0_1") (pintype "bidirectional"))
    )
    (net (code "140") (name "RS485_17_RX") (class "Default")
      (node (ref "RS-485-2") (pin "RO") (pinfunction "R0_RO") (pintype "bidirectional"))
      (node (ref "U7_MUX") (pin "14") (pinfunction "1Y1_14") (pintype "bidirectional"))
    )
    (net (code "141") (name "RS485_17_TX") (class "Default")
      (node (ref "RS-485-2") (pin "DI") (pinfunction "DI_DI") (pintype "bidirectional"))
      (node (ref "U7_MUX") (pin "5") (pinfunction "2Y1_5") (pintype "bidirectional"))
    )
    (net (code "142") (name "RS485_18_RX") (class "Default")
      (node (ref "RS-485-4") (pin "RO") (pinfunction "R0_RO") (pintype "bidirectional"))
      (node (ref "U7_MUX") (pin "15") (pinfunction "1Y2_15") (pintype "bidirectional"))
    )
    (net (code "143") (name "RS485_18_TX") (class "Default")
      (node (ref "RS-485-4") (pin "DI") (pinfunction "DI_DI") (pintype "bidirectional"))
      (node (ref "U7_MUX") (pin "2") (pinfunction "2Y2_2") (pintype "bidirectional"))
    )
    (net (code "144") (name "TCP_INT") (class "Default")
      (node (ref "U$3") (pin "PD2") (pinfunction "PD2_PD2") (pintype "bidirectional"))
      (node (ref "U1") (pin "28") (pinfunction "/INT_28") (pintype "bidirectional"))
    )
    (net (code "145") (name "TCP_MISO") (class "Default")
      (node (ref "U$3") (pin "PA4") (pinfunction "PA4_PA4") (pintype "bidirectional"))
      (node (ref "U1") (pin "2") (pinfunction "MISO_2") (pintype "bidirectional"))
    )
    (net (code "146") (name "TCP_MOSI") (class "Default")
      (node (ref "U$3") (pin "PA5") (pinfunction "PA5_PA5") (pintype "bidirectional"))
      (node (ref "U1") (pin "1") (pinfunction "MOSI_1") (pintype "bidirectional"))
    )
    (net (code "147") (name "TCP_SCLK") (class "Default")
      (node (ref "U$3") (pin "PA2") (pinfunction "PA2_PA2") (pintype "bidirectional"))
      (node (ref "U1") (pin "23") (pinfunction "SCLK_23") (pintype "bidirectional"))
    )
    (net (code "148") (name "TCP_SS") (class "Default")
      (node (ref "U$3") (pin "PA3") (pinfunction "PA3_PA3") (pintype "bidirectional"))
      (node (ref "U1") (pin "24") (pinfunction "/SCS_24") (pintype "bidirectional"))
    )
    (net (code "149") (name "TEMP") (class "Default")
      (node (ref "R38") (pin "1") (pinfunction "1_1") (pintype "passive"))
      (node (ref "TEMP") (pin "2") (pinfunction "2_2") (pintype "passive"))
      (node (ref "U2") (pin "23") (pinfunction "PC0(ADC0)_23") (pintype "bidirectional"))
    )
    (net (code "150") (name "U1RX") (class "Default")
      (node (ref "U$3") (pin "PB0") (pinfunction "PB0_PB0") (pintype "bidirectional"))
      (node (ref "U1_MUX") (pin "13") (pinfunction "1Z_13") (pintype "bidirectional"))
    )
    (net (code "151") (name "U1TX") (class "Default")
      (node (ref "U$3") (pin "PB1") (pinfunction "PB1_PB1") (pintype "bidirectional"))
      (node (ref "U1_MUX") (pin "3") (pinfunction "2Z_3") (pintype "bidirectional"))
    )
    (net (code "152") (name "U1_MUX_S0") (class "Default")
      (node (ref "U$3") (pin "PA6") (pinfunction "PA6_PA6") (pintype "bidirectional"))
      (node (ref "U1_MUX") (pin "10") (pinfunction "S0_10") (pintype "input"))
    )
    (net (code "153") (name "U1_MUX_S1") (class "Default")
      (node (ref "U$3") (pin "PA7") (pinfunction "PA7_PA7") (pintype "bidirectional"))
      (node (ref "U1_MUX") (pin "9") (pinfunction "S1_9") (pintype "input"))
    )
    (net (code "154") (name "U2RX") (class "Default")
      (node (ref "U$3") (pin "PD6") (pinfunction "PD6_PD6") (pintype "bidirectional"))
      (node (ref "U2_MUX") (pin "13") (pinfunction "1Z_13") (pintype "bidirectional"))
    )
    (net (code "155") (name "U2TX") (class "Default")
      (node (ref "U$3") (pin "PD7") (pinfunction "PD7_PD7") (pintype "bidirectional"))
      (node (ref "U2_MUX") (pin "3") (pinfunction "2Z_3") (pintype "bidirectional"))
    )
    (net (code "156") (name "U2_MUX_S0") (class "Default")
      (node (ref "U$3") (pin "PE2") (pinfunction "PE2_PE2") (pintype "bidirectional"))
      (node (ref "U2_MUX") (pin "10") (pinfunction "S0_10") (pintype "input"))
    )
    (net (code "157") (name "U2_MUX_S1") (class "Default")
      (node (ref "U$3") (pin "PE3") (pinfunction "PE3_PE3") (pintype "bidirectional"))
      (node (ref "U2_MUX") (pin "9") (pinfunction "S1_9") (pintype "input"))
    )
    (net (code "158") (name "U3RX") (class "Default")
      (node (ref "U$3") (pin "PC6") (pinfunction "PC6_PC6") (pintype "bidirectional"))
      (node (ref "U3_MUX") (pin "13") (pinfunction "1Z_13") (pintype "bidirectional"))
    )
    (net (code "159") (name "U3TX") (class "Default")
      (node (ref "U$3") (pin "PC7") (pinfunction "PC7_PC7") (pintype "bidirectional"))
      (node (ref "U3_MUX") (pin "3") (pinfunction "2Z_3") (pintype "bidirectional"))
    )
    (net (code "160") (name "U3_MUX_S0") (class "Default")
      (node (ref "U$3") (pin "PB2") (pinfunction "PB2_PB2") (pintype "bidirectional"))
      (node (ref "U3_MUX") (pin "10") (pinfunction "S0_10") (pintype "input"))
    )
    (net (code "161") (name "U3_MUX_S1") (class "Default")
      (node (ref "U$3") (pin "PB3") (pinfunction "PB3_PB3") (pintype "bidirectional"))
      (node (ref "U3_MUX") (pin "9") (pinfunction "S1_9") (pintype "input"))
    )
    (net (code "162") (name "U4RX") (class "Default")
      (node (ref "U$3") (pin "PC4") (pinfunction "PC4_PC4") (pintype "bidirectional"))
      (node (ref "U4_MUX") (pin "13") (pinfunction "1Z_13") (pintype "bidirectional"))
    )
    (net (code "163") (name "U4TX") (class "Default")
      (node (ref "U$3") (pin "PC5") (pinfunction "PC5_PC5") (pintype "bidirectional"))
      (node (ref "U4_MUX") (pin "3") (pinfunction "2Z_3") (pintype "bidirectional"))
    )
    (net (code "164") (name "U4_MUX_S0") (class "Default")
      (node (ref "U$3") (pin "PB4") (pinfunction "PB4_PB4") (pintype "bidirectional"))
      (node (ref "U4_MUX") (pin "10") (pinfunction "S0_10") (pintype "input"))
    )
    (net (code "165") (name "U4_MUX_S1") (class "Default")
      (node (ref "U$3") (pin "PB5") (pinfunction "PB5_PB5") (pintype "bidirectional"))
      (node (ref "U4_MUX") (pin "9") (pinfunction "S1_9") (pintype "input"))
    )
    (net (code "166") (name "U5RX") (class "Default")
      (node (ref "U$3") (pin "PE4") (pinfunction "PE4_PE4") (pintype "bidirectional"))
      (node (ref "U5_MUX") (pin "13") (pinfunction "1Z_13") (pintype "bidirectional"))
    )
    (net (code "167") (name "U5TX") (class "Default")
      (node (ref "U$3") (pin "PE5") (pinfunction "PE5_PE5") (pintype "bidirectional"))
      (node (ref "U5_MUX") (pin "3") (pinfunction "2Z_3") (pintype "bidirectional"))
    )
    (net (code "168") (name "U5_MUX_S0") (class "Default")
      (node (ref "U$3") (pin "PB6") (pinfunction "PB6_PB6") (pintype "bidirectional"))
      (node (ref "U5_MUX") (pin "10") (pinfunction "S0_10") (pintype "input"))
    )
    (net (code "169") (name "U5_MUX_S1") (class "Default")
      (node (ref "U$3") (pin "PB7") (pinfunction "PB7_PB7") (pintype "bidirectional"))
      (node (ref "U5_MUX") (pin "9") (pinfunction "S1_9") (pintype "input"))
    )
    (net (code "170") (name "U7RX") (class "Default")
      (node (ref "U$3") (pin "PE0") (pinfunction "PE0_PE0") (pintype "bidirectional"))
      (node (ref "U7_MUX") (pin "13") (pinfunction "1Z_13") (pintype "bidirectional"))
    )
    (net (code "171") (name "U7TX") (class "Default")
      (node (ref "U$3") (pin "PE1") (pinfunction "PE1_PE1") (pintype "bidirectional"))
      (node (ref "U7_MUX") (pin "3") (pinfunction "2Z_3") (pintype "bidirectional"))
    )
    (net (code "172") (name "U7_MUX_S0") (class "Default")
      (node (ref "U$3") (pin "PD0") (pinfunction "PD0_PD0") (pintype "bidirectional"))
      (node (ref "U7_MUX") (pin "10") (pinfunction "S0_10") (pintype "input"))
    )
    (net (code "173") (name "U7_MUX_S1") (class "Default")
      (node (ref "U$3") (pin "PD1") (pinfunction "PD1_PD1") (pintype "bidirectional"))
      (node (ref "U7_MUX") (pin "9") (pinfunction "S1_9") (pintype "input"))
    )
    (net (code "174") (name "unconnected-(BLUETOOTH-PadBOOT)") (class "Default")
      (node (ref "BLUETOOTH") (pin "BOOT") (pinfunction "BOOT_BOOT") (pintype "bidirectional"))
    )
    (net (code "175") (name "unconnected-(BLUETOOTH-PadGPIO1)") (class "Default")
      (node (ref "BLUETOOTH") (pin "GPIO1") (pinfunction "GPIO1_GPIO1") (pintype "bidirectional"))
    )
    (net (code "176") (name "unconnected-(BLUETOOTH-PadGPIO2)") (class "Default")
      (node (ref "BLUETOOTH") (pin "GPIO2") (pinfunction "GPIO2_GPIO2") (pintype "bidirectional"))
    )
    (net (code "177") (name "unconnected-(BLUETOOTH-PadGPIO3)") (class "Default")
      (node (ref "BLUETOOTH") (pin "GPIO3") (pinfunction "GPIO3_GPIO3") (pintype "bidirectional"))
    )
    (net (code "178") (name "unconnected-(BLUETOOTH-PadGPIO4)") (class "Default")
      (node (ref "BLUETOOTH") (pin "GPIO4") (pinfunction "GPIO4_GPIO4") (pintype "bidirectional"))
    )
    (net (code "179") (name "unconnected-(BLUETOOTH-PadGPIO5)") (class "Default")
      (node (ref "BLUETOOTH") (pin "GPIO5") (pinfunction "GPIO5_GPIO5") (pintype "bidirectional"))
    )
    (net (code "180") (name "unconnected-(BLUETOOTH-PadGPIO6)") (class "Default")
      (node (ref "BLUETOOTH") (pin "GPIO6") (pinfunction "GPIO6_GPIO6") (pintype "bidirectional"))
    )
    (net (code "181") (name "unconnected-(BLUETOOTH-PadGPIO7)") (class "Default")
      (node (ref "BLUETOOTH") (pin "GPIO7") (pinfunction "GPIO7_GPIO7") (pintype "bidirectional"))
    )
    (net (code "182") (name "unconnected-(BLUETOOTH-PadLPO)") (class "Default")
      (node (ref "BLUETOOTH") (pin "LPO") (pinfunction "LPO_LPO") (pintype "bidirectional"))
    )
    (net (code "183") (name "unconnected-(FAN1-Pad3)") (class "Default")
      (node (ref "FAN1") (pin "3") (pinfunction "3_3") (pintype "passive"))
    )
    (net (code "184") (name "unconnected-(FAN1-Pad4)") (class "Default")
      (node (ref "FAN1") (pin "4") (pinfunction "4_4") (pintype "passive"))
    )
    (net (code "185") (name "unconnected-(FAN2-Pad3)") (class "Default")
      (node (ref "FAN2") (pin "3") (pinfunction "3_3") (pintype "passive"))
    )
    (net (code "186") (name "unconnected-(FAN2-Pad4)") (class "Default")
      (node (ref "FAN2") (pin "4") (pinfunction "4_4") (pintype "passive"))
    )
    (net (code "187") (name "unconnected-(FAN3-Pad3)") (class "Default")
      (node (ref "FAN3") (pin "3") (pinfunction "3_3") (pintype "passive"))
    )
    (net (code "188") (name "unconnected-(FAN3-Pad4)") (class "Default")
      (node (ref "FAN3") (pin "4") (pinfunction "4_4") (pintype "passive"))
    )
    (net (code "189") (name "unconnected-(FAN4-Pad3)") (class "Default")
      (node (ref "FAN4") (pin "3") (pinfunction "3_3") (pintype "passive"))
    )
    (net (code "190") (name "unconnected-(FAN4-Pad4)") (class "Default")
      (node (ref "FAN4") (pin "4") (pinfunction "4_4") (pintype "passive"))
    )
    (net (code "191") (name "unconnected-(GPS-1PPS-PadP$13)") (class "Default")
      (node (ref "GPS") (pin "P$13") (pinfunction "1PPS_P$13") (pintype "bidirectional"))
    )
    (net (code "192") (name "unconnected-(GPS-NC-PadP$6)") (class "Default")
      (node (ref "GPS") (pin "P$6") (pinfunction "NC_P$6") (pintype "bidirectional"))
    )
    (net (code "193") (name "unconnected-(GPS-NC-PadP$7)") (class "Default")
      (node (ref "GPS") (pin "P$7") (pinfunction "NC_P$7") (pintype "bidirectional"))
    )
    (net (code "194") (name "unconnected-(GPS-NC-PadP$15)") (class "Default")
      (node (ref "GPS") (pin "P$15") (pinfunction "NC_P$15") (pintype "bidirectional"))
    )
    (net (code "195") (name "unconnected-(GPS-NC-PadP$16)") (class "Default")
      (node (ref "GPS") (pin "P$16") (pinfunction "NC_P$16") (pintype "bidirectional"))
    )
    (net (code "196") (name "unconnected-(GPS-NC-PadP$17)") (class "Default")
      (node (ref "GPS") (pin "P$17") (pinfunction "NC_P$17") (pintype "bidirectional"))
    )
    (net (code "197") (name "unconnected-(GPS-NC-PadP$18)") (class "Default")
      (node (ref "GPS") (pin "P$18") (pinfunction "NC_P$18") (pintype "bidirectional"))
    )
    (net (code "198") (name "unconnected-(GPS-NC-PadP$20)") (class "Default")
      (node (ref "GPS") (pin "P$20") (pinfunction "NC_P$20") (pintype "bidirectional"))
    )
    (net (code "199") (name "unconnected-(GPS-NRESET-PadP$2)") (class "Default")
      (node (ref "GPS") (pin "P$2") (pinfunction "NRESET_P$2") (pintype "bidirectional"))
    )
    (net (code "200") (name "unconnected-(GPS-RTCM-PadP$14)") (class "Default")
      (node (ref "GPS") (pin "P$14") (pinfunction "RTCM_P$14") (pintype "bidirectional"))
    )
    (net (code "201") (name "unconnected-(GPS-VBACKUP-PadP$4)") (class "Default")
      (node (ref "GPS") (pin "P$4") (pinfunction "VBACKUP_P$4") (pintype "bidirectional"))
    )
    (net (code "202") (name "unconnected-(H1-Pad1)") (class "Default")
      (node (ref "H1") (pin "1") (pinfunction "1_1") (pintype "passive"))
    )
    (net (code "203") (name "unconnected-(H2-Pad1)") (class "Default")
      (node (ref "H2") (pin "1") (pinfunction "1_1") (pintype "passive"))
    )
    (net (code "204") (name "unconnected-(H3-Pad1)") (class "Default")
      (node (ref "H3") (pin "1") (pinfunction "1_1") (pintype "passive"))
    )
    (net (code "205") (name "unconnected-(H4-Pad1)") (class "Default")
      (node (ref "H4") (pin "1") (pinfunction "1_1") (pintype "passive"))
    )
    (net (code "206") (name "unconnected-(LCD-Pad7)") (class "Default")
      (node (ref "LCD") (pin "7") (pinfunction "7_7") (pintype "passive"))
    )
    (net (code "207") (name "unconnected-(LCD-Pad8)") (class "Default")
      (node (ref "LCD") (pin "8") (pinfunction "8_8") (pintype "passive"))
    )
    (net (code "208") (name "unconnected-(LCD-Pad9)") (class "Default")
      (node (ref "LCD") (pin "9") (pinfunction "9_9") (pintype "passive"))
    )
    (net (code "209") (name "unconnected-(LCD-Pad10)") (class "Default")
      (node (ref "LCD") (pin "10") (pinfunction "10_10") (pintype "passive"))
    )
    (net (code "210") (name "unconnected-(S1-O-Pad1)") (class "Default")
      (node (ref "S1") (pin "1") (pinfunction "O_1") (pintype "passive"))
    )
    (net (code "211") (name "unconnected-(U$4-Pad49)") (class "Default")
      (node (ref "U$4") (pin "49") (pinfunction "49_49") (pintype "bidirectional"))
    )
    (net (code "212") (name "unconnected-(U$4-Pad50)") (class "Default")
      (node (ref "U$4") (pin "50") (pinfunction "50_50") (pintype "bidirectional"))
    )
    (net (code "213") (name "unconnected-(U$4-Pad51)") (class "Default")
      (node (ref "U$4") (pin "51") (pinfunction "51_51") (pintype "bidirectional"))
    )
    (net (code "214") (name "unconnected-(U$4-Pad52)") (class "Default")
      (node (ref "U$4") (pin "52") (pinfunction "52_52") (pintype "bidirectional"))
    )
    (net (code "215") (name "unconnected-(U$4-Pad53)") (class "Default")
      (node (ref "U$4") (pin "53") (pinfunction "53_53") (pintype "bidirectional"))
    )
    (net (code "216") (name "unconnected-(U$4-Pad54)") (class "Default")
      (node (ref "U$4") (pin "54") (pinfunction "54_54") (pintype "bidirectional"))
    )
    (net (code "217") (name "unconnected-(U$4-Pad55)") (class "Default")
      (node (ref "U$4") (pin "55") (pinfunction "55_55") (pintype "bidirectional"))
    )
    (net (code "218") (name "unconnected-(U$4-Pad56)") (class "Default")
      (node (ref "U$4") (pin "56") (pinfunction "56_56") (pintype "bidirectional"))
    )
    (net (code "219") (name "unconnected-(U$4-Pad57)") (class "Default")
      (node (ref "U$4") (pin "57") (pinfunction "57_57") (pintype "bidirectional"))
    )
    (net (code "220") (name "unconnected-(U$4-Pad58)") (class "Default")
      (node (ref "U$4") (pin "58") (pinfunction "58_58") (pintype "bidirectional"))
    )
    (net (code "221") (name "unconnected-(U$4-Pad59)") (class "Default")
      (node (ref "U$4") (pin "59") (pinfunction "59_59") (pintype "bidirectional"))
    )
    (net (code "222") (name "unconnected-(U$4-Pad60)") (class "Default")
      (node (ref "U$4") (pin "60") (pinfunction "60_60") (pintype "bidirectional"))
    )
    (net (code "223") (name "unconnected-(U$4-Pad61)") (class "Default")
      (node (ref "U$4") (pin "61") (pinfunction "61_61") (pintype "bidirectional"))
    )
    (net (code "224") (name "unconnected-(U$4-Pad62)") (class "Default")
      (node (ref "U$4") (pin "62") (pinfunction "62_62") (pintype "bidirectional"))
    )
    (net (code "225") (name "unconnected-(U$4-Pad63)") (class "Default")
      (node (ref "U$4") (pin "63") (pinfunction "63_63") (pintype "bidirectional"))
    )
    (net (code "226") (name "unconnected-(U$4-Pad64)") (class "Default")
      (node (ref "U$4") (pin "64") (pinfunction "64_64") (pintype "bidirectional"))
    )
    (net (code "227") (name "unconnected-(U$4-Pad65)") (class "Default")
      (node (ref "U$4") (pin "65") (pinfunction "65_65") (pintype "bidirectional"))
    )
    (net (code "228") (name "unconnected-(U$4-Pad66)") (class "Default")
      (node (ref "U$4") (pin "66") (pinfunction "66_66") (pintype "bidirectional"))
    )
    (net (code "229") (name "unconnected-(U$4-Pad67)") (class "Default")
      (node (ref "U$4") (pin "67") (pinfunction "67_67") (pintype "bidirectional"))
    )
    (net (code "230") (name "unconnected-(U$4-Pad68)") (class "Default")
      (node (ref "U$4") (pin "68") (pinfunction "68_68") (pintype "bidirectional"))
    )
    (net (code "231") (name "unconnected-(U$5-Pad4)") (class "Default")
      (node (ref "U$5") (pin "4") (pinfunction "4_4") (pintype "bidirectional"))
    )
    (net (code "232") (name "unconnected-(U$5-Pad5)") (class "Default")
      (node (ref "U$5") (pin "5") (pinfunction "5_5") (pintype "bidirectional"))
    )
    (net (code "233") (name "unconnected-(U$5-Pad7)") (class "Default")
      (node (ref "U$5") (pin "7") (pinfunction "7_7") (pintype "bidirectional"))
    )
    (net (code "234") (name "unconnected-(U$5-Pad8)") (class "Default")
      (node (ref "U$5") (pin "8") (pinfunction "8_8") (pintype "bidirectional"))
    )
    (net (code "235") (name "unconnected-(U$6-Pad4)") (class "Default")
      (node (ref "U$6") (pin "4") (pinfunction "4_4") (pintype "bidirectional"))
    )
    (net (code "236") (name "unconnected-(U$6-Pad5)") (class "Default")
      (node (ref "U$6") (pin "5") (pinfunction "5_5") (pintype "bidirectional"))
    )
    (net (code "237") (name "unconnected-(U$6-Pad7)") (class "Default")
      (node (ref "U$6") (pin "7") (pinfunction "7_7") (pintype "bidirectional"))
    )
    (net (code "238") (name "unconnected-(U$6-Pad8)") (class "Default")
      (node (ref "U$6") (pin "8") (pinfunction "8_8") (pintype "bidirectional"))
    )
    (net (code "239") (name "unconnected-(U$7-Pad4)") (class "Default")
      (node (ref "U$7") (pin "4") (pinfunction "4_4") (pintype "bidirectional"))
    )
    (net (code "240") (name "unconnected-(U$7-Pad5)") (class "Default")
      (node (ref "U$7") (pin "5") (pinfunction "5_5") (pintype "bidirectional"))
    )
    (net (code "241") (name "unconnected-(U$7-Pad7)") (class "Default")
      (node (ref "U$7") (pin "7") (pinfunction "7_7") (pintype "bidirectional"))
    )
    (net (code "242") (name "unconnected-(U$7-Pad8)") (class "Default")
      (node (ref "U$7") (pin "8") (pinfunction "8_8") (pintype "bidirectional"))
    )
    (net (code "243") (name "unconnected-(U$8-Pad4)") (class "Default")
      (node (ref "U$8") (pin "4") (pinfunction "4_4") (pintype "bidirectional"))
    )
    (net (code "244") (name "unconnected-(U$8-Pad5)") (class "Default")
      (node (ref "U$8") (pin "5") (pinfunction "5_5") (pintype "bidirectional"))
    )
    (net (code "245") (name "unconnected-(U$8-Pad7)") (class "Default")
      (node (ref "U$8") (pin "7") (pinfunction "7_7") (pintype "bidirectional"))
    )
    (net (code "246") (name "unconnected-(U$8-Pad8)") (class "Default")
      (node (ref "U$8") (pin "8") (pinfunction "8_8") (pintype "bidirectional"))
    )
    (net (code "247") (name "unconnected-(U$9-Pad4)") (class "Default")
      (node (ref "U$9") (pin "4") (pinfunction "4_4") (pintype "bidirectional"))
    )
    (net (code "248") (name "unconnected-(U$9-Pad5)") (class "Default")
      (node (ref "U$9") (pin "5") (pinfunction "5_5") (pintype "bidirectional"))
    )
    (net (code "249") (name "unconnected-(U$9-Pad7)") (class "Default")
      (node (ref "U$9") (pin "7") (pinfunction "7_7") (pintype "bidirectional"))
    )
    (net (code "250") (name "unconnected-(U$9-Pad8)") (class "Default")
      (node (ref "U$9") (pin "8") (pinfunction "8_8") (pintype "bidirectional"))
    )
    (net (code "251") (name "unconnected-(U$10-Pad4)") (class "Default")
      (node (ref "U$10") (pin "4") (pinfunction "4_4") (pintype "bidirectional"))
    )
    (net (code "252") (name "unconnected-(U$10-Pad5)") (class "Default")
      (node (ref "U$10") (pin "5") (pinfunction "5_5") (pintype "bidirectional"))
    )
    (net (code "253") (name "unconnected-(U$10-Pad7)") (class "Default")
      (node (ref "U$10") (pin "7") (pinfunction "7_7") (pintype "bidirectional"))
    )
    (net (code "254") (name "unconnected-(U$10-Pad8)") (class "Default")
      (node (ref "U$10") (pin "8") (pinfunction "8_8") (pintype "bidirectional"))
    )
    (net (code "255") (name "unconnected-(U1-A0-Pad31)") (class "Default")
      (node (ref "U1") (pin "31") (pinfunction "A0_31") (pintype "bidirectional"))
    )
    (net (code "256") (name "unconnected-(U1-A1-Pad32)") (class "Default")
      (node (ref "U1") (pin "32") (pinfunction "A1_32") (pintype "bidirectional"))
    )
    (net (code "257") (name "unconnected-(U1-A2-Pad33)") (class "Default")
      (node (ref "U1") (pin "33") (pinfunction "A2_33") (pintype "bidirectional"))
    )
    (net (code "258") (name "unconnected-(U1-A3-Pad34)") (class "Default")
      (node (ref "U1") (pin "34") (pinfunction "A3_34") (pintype "bidirectional"))
    )
    (net (code "259") (name "unconnected-(U1-A4-Pad35)") (class "Default")
      (node (ref "U1") (pin "35") (pinfunction "A4_35") (pintype "bidirectional"))
    )
    (net (code "260") (name "unconnected-(U1-A5-Pad36)") (class "Default")
      (node (ref "U1") (pin "36") (pinfunction "A5_36") (pintype "bidirectional"))
    )
    (net (code "261") (name "unconnected-(U1-A6-Pad37)") (class "Default")
      (node (ref "U1") (pin "37") (pinfunction "A6_37") (pintype "bidirectional"))
    )
    (net (code "262") (name "unconnected-(U1-A7-Pad38)") (class "Default")
      (node (ref "U1") (pin "38") (pinfunction "A7_38") (pintype "bidirectional"))
    )
    (net (code "263") (name "unconnected-(U1-A8-Pad13)") (class "Default")
      (node (ref "U1") (pin "13") (pinfunction "A8_13") (pintype "bidirectional"))
    )
    (net (code "264") (name "unconnected-(U1-A9-Pad14)") (class "Default")
      (node (ref "U1") (pin "14") (pinfunction "A9_14") (pintype "bidirectional"))
    )
    (net (code "265") (name "unconnected-(U1-A10-Pad15)") (class "Default")
      (node (ref "U1") (pin "15") (pinfunction "A10_15") (pintype "bidirectional"))
    )
    (net (code "266") (name "unconnected-(U1-A11-Pad16)") (class "Default")
      (node (ref "U1") (pin "16") (pinfunction "A11_16") (pintype "bidirectional"))
    )
    (net (code "267") (name "unconnected-(U1-A12-Pad17)") (class "Default")
      (node (ref "U1") (pin "17") (pinfunction "A12_17") (pintype "bidirectional"))
    )
    (net (code "268") (name "unconnected-(U1-A13-Pad18)") (class "Default")
      (node (ref "U1") (pin "18") (pinfunction "A13_18") (pintype "bidirectional"))
    )
    (net (code "269") (name "unconnected-(U1-A14-Pad19)") (class "Default")
      (node (ref "U1") (pin "19") (pinfunction "A14_19") (pintype "bidirectional"))
    )
    (net (code "270") (name "unconnected-(U1-D0-Pad4)") (class "Default")
      (node (ref "U1") (pin "4") (pinfunction "D0_4") (pintype "bidirectional"))
    )
    (net (code "271") (name "unconnected-(U1-D1-Pad3)") (class "Default")
      (node (ref "U1") (pin "3") (pinfunction "D1_3") (pintype "bidirectional"))
    )
    (net (code "272") (name "unconnected-(U1-D2-Pad6)") (class "Default")
      (node (ref "U1") (pin "6") (pinfunction "D2_6") (pintype "bidirectional"))
    )
    (net (code "273") (name "unconnected-(U1-D3-Pad5)") (class "Default")
      (node (ref "U1") (pin "5") (pinfunction "D3_5") (pintype "bidirectional"))
    )
    (net (code "274") (name "unconnected-(U1-D4-Pad8)") (class "Default")
      (node (ref "U1") (pin "8") (pinfunction "D4_8") (pintype "bidirectional"))
    )
    (net (code "275") (name "unconnected-(U1-D5-Pad7)") (class "Default")
      (node (ref "U1") (pin "7") (pinfunction "D5_7") (pintype "bidirectional"))
    )
    (net (code "276") (name "unconnected-(U1-D6-Pad10)") (class "Default")
      (node (ref "U1") (pin "10") (pinfunction "D6_10") (pintype "bidirectional"))
    )
    (net (code "277") (name "unconnected-(U1-D7-Pad9)") (class "Default")
      (node (ref "U1") (pin "9") (pinfunction "D7_9") (pintype "bidirectional"))
    )
    (net (code "278") (name "unconnected-(U1-{slash}CS-Pad27)") (class "Default")
      (node (ref "U1") (pin "27") (pinfunction "/CS_27") (pintype "bidirectional"))
    )
    (net (code "279") (name "unconnected-(U1-{slash}RD-Pad26)") (class "Default")
      (node (ref "U1") (pin "26") (pinfunction "/RD_26") (pintype "bidirectional"))
    )
    (net (code "280") (name "unconnected-(U1-{slash}WR-Pad25)") (class "Default")
      (node (ref "U1") (pin "25") (pinfunction "/WR_25") (pintype "bidirectional"))
    )
    (net (code "281") (name "unconnected-(U1_MUX-1Y3-Pad11)") (class "Default")
      (node (ref "U1_MUX") (pin "11") (pinfunction "1Y3_11") (pintype "bidirectional"))
    )
    (net (code "282") (name "unconnected-(U1_MUX-2Y3-Pad4)") (class "Default")
      (node (ref "U1_MUX") (pin "4") (pinfunction "2Y3_4") (pintype "bidirectional"))
    )
    (net (code "283") (name "unconnected-(U2-PB0(ICP)-Pad14)") (class "Default")
      (node (ref "U2") (pin "14") (pinfunction "PB0(ICP)_14") (pintype "bidirectional"))
    )
    (net (code "284") (name "unconnected-(U2-PB1(OC1A)-Pad15)") (class "Default")
      (node (ref "U2") (pin "15") (pinfunction "PB1(OC1A)_15") (pintype "bidirectional"))
    )
    (net (code "285") (name "unconnected-(U2-PB2(SS{slash}OC1B)-Pad16)") (class "Default")
      (node (ref "U2") (pin "16") (pinfunction "PB2(SS/OC1B)_16") (pintype "bidirectional"))
    )
    (net (code "286") (name "unconnected-(U2-PC1(ADC1)-Pad24)") (class "Default")
      (node (ref "U2") (pin "24") (pinfunction "PC1(ADC1)_24") (pintype "bidirectional"))
    )
    (net (code "287") (name "unconnected-(U2-PC2(ADC2)-Pad25)") (class "Default")
      (node (ref "U2") (pin "25") (pinfunction "PC2(ADC2)_25") (pintype "bidirectional"))
    )
    (net (code "288") (name "unconnected-(U2-PC3(ADC3)-Pad26)") (class "Default")
      (node (ref "U2") (pin "26") (pinfunction "PC3(ADC3)_26") (pintype "bidirectional"))
    )
    (net (code "289") (name "unconnected-(U2-PC4(ADC4{slash}SDA)-Pad27)") (class "Default")
      (node (ref "U2") (pin "27") (pinfunction "PC4(ADC4/SDA)_27") (pintype "bidirectional"))
    )
    (net (code "290") (name "unconnected-(U2-PC5(ADC5{slash}SCL)-Pad28)") (class "Default")
      (node (ref "U2") (pin "28") (pinfunction "PC5(ADC5/SCL)_28") (pintype "bidirectional"))
    )
    (net (code "291") (name "unconnected-(U2_MUX-1Y3-Pad11)") (class "Default")
      (node (ref "U2_MUX") (pin "11") (pinfunction "1Y3_11") (pintype "bidirectional"))
    )
    (net (code "292") (name "unconnected-(U2_MUX-2Y3-Pad4)") (class "Default")
      (node (ref "U2_MUX") (pin "4") (pinfunction "2Y3_4") (pintype "bidirectional"))
    )
    (net (code "293") (name "unconnected-(U3_MUX-1Y3-Pad11)") (class "Default")
      (node (ref "U3_MUX") (pin "11") (pinfunction "1Y3_11") (pintype "bidirectional"))
    )
    (net (code "294") (name "unconnected-(U3_MUX-2Y3-Pad4)") (class "Default")
      (node (ref "U3_MUX") (pin "4") (pinfunction "2Y3_4") (pintype "bidirectional"))
    )
    (net (code "295") (name "unconnected-(U4_MUX-1Y3-Pad11)") (class "Default")
      (node (ref "U4_MUX") (pin "11") (pinfunction "1Y3_11") (pintype "bidirectional"))
    )
    (net (code "296") (name "unconnected-(U4_MUX-2Y3-Pad4)") (class "Default")
      (node (ref "U4_MUX") (pin "4") (pinfunction "2Y3_4") (pintype "bidirectional"))
    )
    (net (code "297") (name "unconnected-(U7_MUX-1Y3-Pad11)") (class "Default")
      (node (ref "U7_MUX") (pin "11") (pinfunction "1Y3_11") (pintype "bidirectional"))
    )
    (net (code "298") (name "unconnected-(U7_MUX-2Y3-Pad4)") (class "Default")
      (node (ref "U7_MUX") (pin "4") (pinfunction "2Y3_4") (pintype "bidirectional"))
    )
  )
)
